# Laser_Array.net
KiCad netlist of a schematic drawn in EAGLE
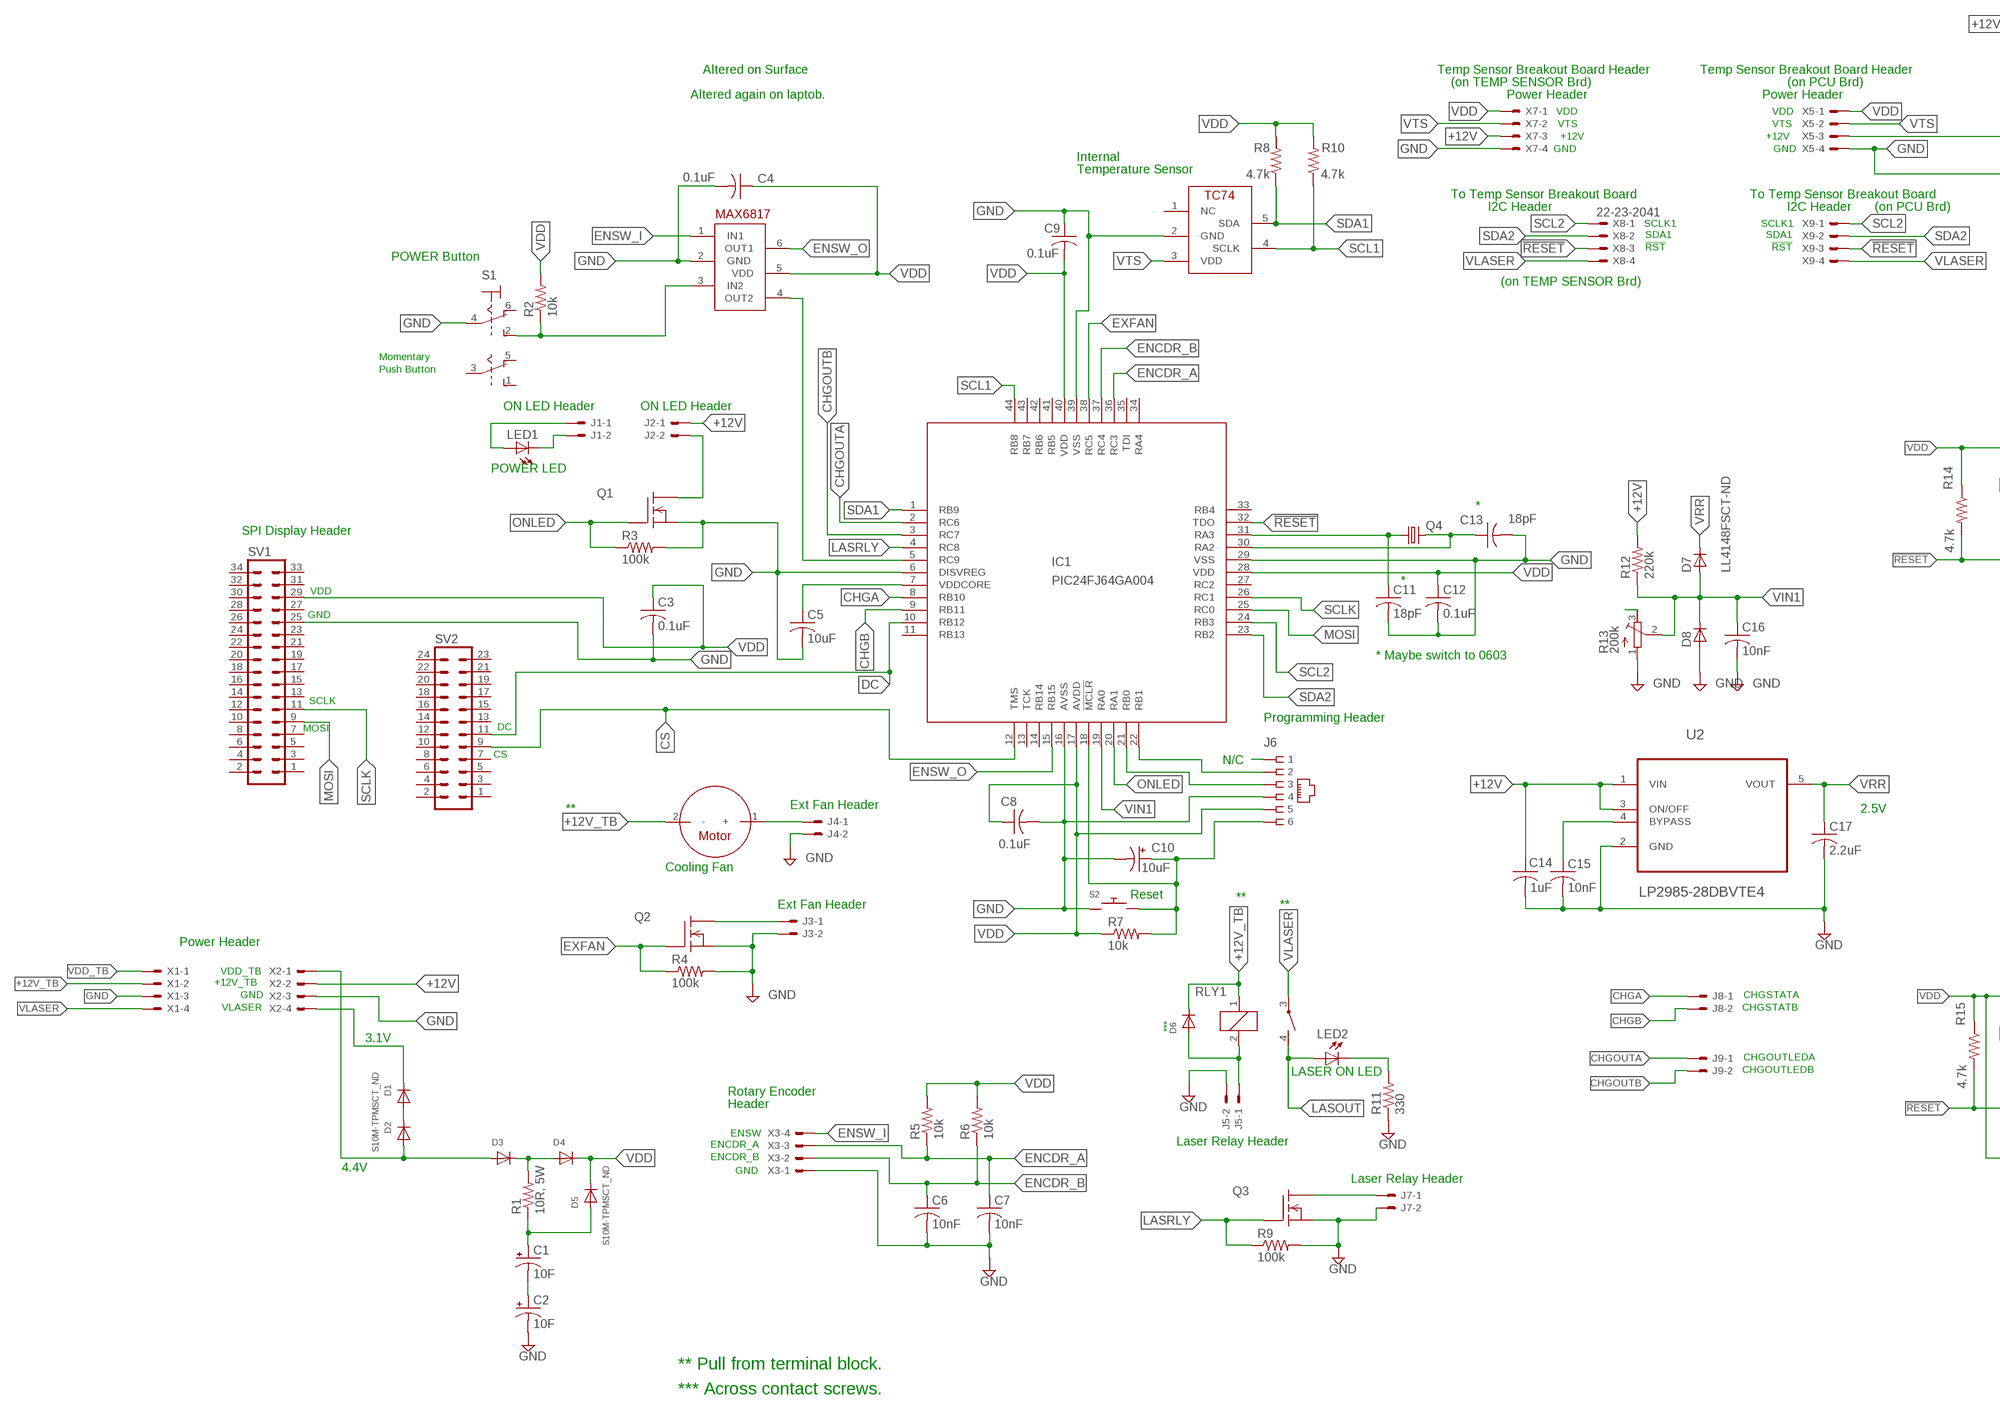
[diagram p0: schematic, sheet 1, part 1 of 2]
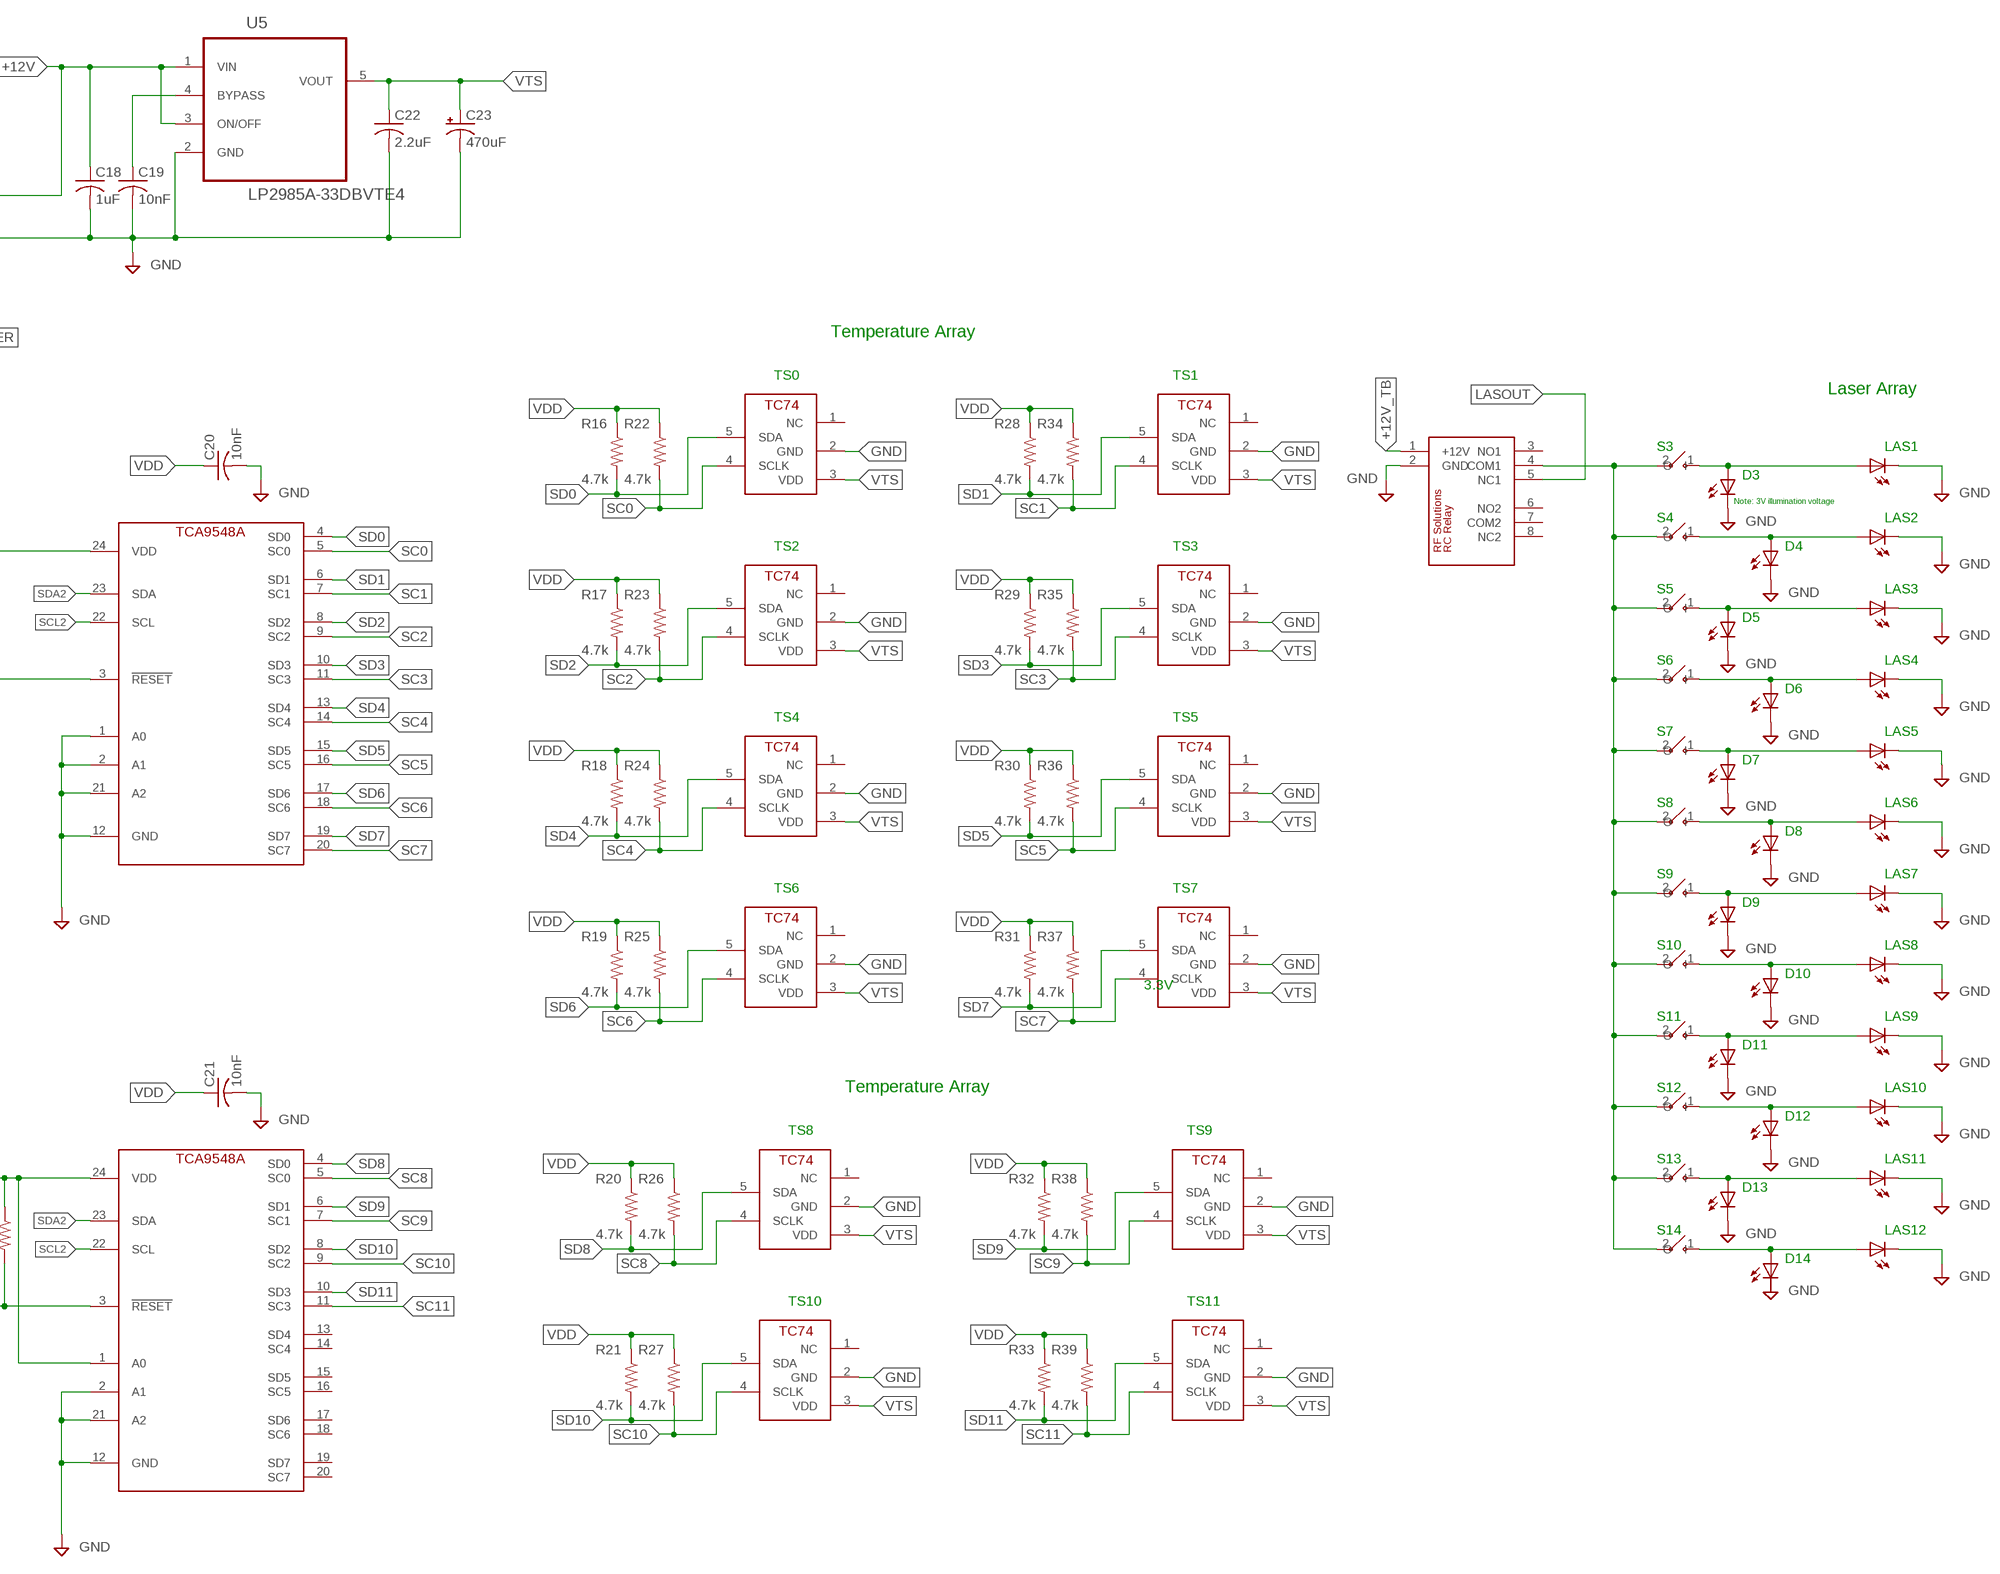
[diagram p1: schematic, sheet 1, part 2 of 2]

(export (version "E")
  (design (tool "Eeschema 10.0.6"))
  (components
    (comp (ref "C1")
      (value "10F")
      (footprint "eagle-import:E5-10,5")
      (libsource (lib "eagle-import") (part "CPOL-USE5-10.5"))
    )
    (comp (ref "C2")
      (value "10F")
      (footprint "eagle-import:E5-10,5")
      (libsource (lib "eagle-import") (part "CPOL-USE5-10.5"))
    )
    (comp (ref "C3")
      (value "0.1uF")
      (footprint "eagle-import:C0805")
      (libsource (lib "eagle-import") (part "C-USC0805"))
    )
    (comp (ref "C4")
      (value "0.1uF")
      (footprint "eagle-import:C0805")
      (libsource (lib "eagle-import") (part "C-USC0805"))
    )
    (comp (ref "C5")
      (value "10uF")
      (footprint "eagle-import:C0805")
      (libsource (lib "eagle-import") (part "C-USC0805"))
    )
    (comp (ref "C6")
      (value "10nF")
      (footprint "eagle-import:C0805")
      (libsource (lib "eagle-import") (part "C-USC0805"))
    )
    (comp (ref "C7")
      (value "10nF")
      (footprint "eagle-import:C0805")
      (libsource (lib "eagle-import") (part "C-USC0805"))
    )
    (comp (ref "C8")
      (value "0.1uF")
      (footprint "eagle-import:C0805")
      (libsource (lib "eagle-import") (part "C-USC0805"))
    )
    (comp (ref "C9")
      (value "0.1uF")
      (footprint "eagle-import:C0805")
      (libsource (lib "eagle-import") (part "C-USC0805"))
    )
    (comp (ref "C10")
      (value "10uF")
      (footprint "eagle-import:CAP3X3")
      (libsource (lib "eagle-import") (part "CAP3X3"))
    )
    (comp (ref "C11")
      (value "18pF")
      (footprint "eagle-import:C0805")
      (libsource (lib "eagle-import") (part "C-USC0805"))
    )
    (comp (ref "C12")
      (value "0.1uF")
      (footprint "eagle-import:C0805")
      (libsource (lib "eagle-import") (part "C-USC0805"))
    )
    (comp (ref "C13")
      (value "18pF")
      (footprint "eagle-import:C0805")
      (libsource (lib "eagle-import") (part "C-USC0805"))
    )
    (comp (ref "C14")
      (value "1uF")
      (footprint "eagle-import:C0805")
      (libsource (lib "eagle-import") (part "C-USC0805"))
    )
    (comp (ref "C15")
      (value "10nF")
      (footprint "eagle-import:C0805")
      (libsource (lib "eagle-import") (part "C-USC0805"))
    )
    (comp (ref "C16")
      (value "10nF")
      (footprint "eagle-import:C0805")
      (libsource (lib "eagle-import") (part "C-USC0805"))
    )
    (comp (ref "C17")
      (value "2.2uF")
      (footprint "eagle-import:C0805")
      (libsource (lib "eagle-import") (part "C-USC0805"))
    )
    (comp (ref "C18")
      (value "1uF")
      (footprint "eagle-import:C0805")
      (libsource (lib "eagle-import") (part "C-USC0805"))
    )
    (comp (ref "C19")
      (value "10nF")
      (footprint "eagle-import:C0805")
      (libsource (lib "eagle-import") (part "C-USC0805"))
    )
    (comp (ref "C20")
      (value "10nF")
      (footprint "eagle-import:C0805")
      (libsource (lib "eagle-import") (part "C-USC0805"))
    )
    (comp (ref "C21")
      (value "10nF")
      (footprint "eagle-import:C0805")
      (libsource (lib "eagle-import") (part "C-USC0805"))
    )
    (comp (ref "C22")
      (value "2.2uF")
      (footprint "eagle-import:C0805")
      (libsource (lib "eagle-import") (part "C-USC0805"))
    )
    (comp (ref "C23")
      (value "470uF")
      (footprint "eagle-import:PANASONIC_F")
      (libsource (lib "eagle-import") (part "CPOL-USF"))
    )
    (comp (ref "D1")
      (value "S10M-TPMSCT_ND")
      (footprint "eagle-import:S10M-TPMSCT-ND")
      (libsource (lib "eagle-import") (part "S10M-TPMSCT_ND"))
    )
    (comp (ref "D2")
      (value "641-1014-6-ND")
      (footprint "eagle-import:SOD-123")
      (libsource (lib "eagle-import") (part "DIODESOD-123"))
    )
    (comp (ref "D3")
      (value "641-1014-6-ND")
      (footprint "eagle-import:SOD-123")
      (libsource (lib "eagle-import") (part "DIODESOD-123"))
    )
    (comp (ref "D4")
      (value "641-1014-6-ND")
      (footprint "eagle-import:SOD-123")
      (libsource (lib "eagle-import") (part "DIODESOD-123"))
    )
    (comp (ref "D5")
      (value "S10M-TPMSCT_ND")
      (footprint "eagle-import:S10M-TPMSCT-ND")
      (libsource (lib "eagle-import") (part "S10M-TPMSCT_ND"))
    )
    (comp (ref "D6")
      (value "641-1014-6-ND")
      (footprint "eagle-import:SOD-123")
      (libsource (lib "eagle-import") (part "DIODESOD-123"))
    )
    (comp (ref "D7")
      (value "LL4148FSCT-ND")
      (footprint "eagle-import:SOD80")
      (libsource (lib "eagle-import") (part "D-SOD-80"))
    )
    (comp (ref "D8")
      (value "LL4148FSCT-ND")
      (footprint "eagle-import:SOD80")
      (libsource (lib "eagle-import") (part "D-SOD-80"))
    )
    (comp (ref "IC1")
      (value "PIC24FJ64GA004")
      (footprint "eagle-import:TQFP44")
      (fields (field (name "MPN") "PIC24FJ64GA004-E/PT"))
      (libsource (lib "eagle-import") (part "PIC24FJ64GA004"))
    )
    (comp (ref "J1")
      (value "22-23-2021")
      (footprint "eagle-import:22-23-2021")
      (fields (field (name "MF") "MOLEX"))
      (libsource (lib "eagle-import") (part "22-23-2021"))
    )
    (comp (ref "J2")
      (value "22-23-2021")
      (footprint "eagle-import:22-23-2021")
      (fields (field (name "MF") "MOLEX"))
      (libsource (lib "eagle-import") (part "22-23-2021"))
    )
    (comp (ref "J3")
      (value "22-23-2021")
      (footprint "eagle-import:22-23-2021")
      (fields (field (name "MF") "MOLEX"))
      (libsource (lib "eagle-import") (part "22-23-2021"))
    )
    (comp (ref "J4")
      (value "22-23-2021")
      (footprint "eagle-import:22-23-2021")
      (fields (field (name "MF") "MOLEX"))
      (libsource (lib "eagle-import") (part "22-23-2021"))
    )
    (comp (ref "J5")
      (value "22-23-2021")
      (footprint "eagle-import:22-23-2021")
      (fields (field (name "MF") "MOLEX"))
      (libsource (lib "eagle-import") (part "22-23-2021"))
    )
    (comp (ref "J6")
      (value "RJ_25")
      (footprint "eagle-import:RJ11-NO_SHIELD")
      (libsource (lib "eagle-import") (part "RJ_25"))
    )
    (comp (ref "J7")
      (value "22-23-2021")
      (footprint "eagle-import:22-23-2021")
      (fields (field (name "MF") "MOLEX"))
      (libsource (lib "eagle-import") (part "22-23-2021"))
    )
    (comp (ref "J8")
      (value "22-23-2021")
      (footprint "eagle-import:22-23-2021")
      (fields (field (name "MF") "MOLEX"))
      (libsource (lib "eagle-import") (part "22-23-2021"))
    )
    (comp (ref "J9")
      (value "22-23-2021")
      (footprint "eagle-import:22-23-2021")
      (fields (field (name "MF") "MOLEX"))
      (libsource (lib "eagle-import") (part "22-23-2021"))
    )
    (comp (ref "LED1")
      (value "LEDA5MM")
      (footprint "eagle-import:LED5MM")
      (libsource (lib "eagle-import") (part "LEDA5MM"))
    )
    (comp (ref "LED2")
      (value "LEDA5MM")
      (footprint "eagle-import:LED5MM")
      (libsource (lib "eagle-import") (part "LEDA5MM"))
    )
    (comp (ref "LED3")
      (value "LED3MM")
      (footprint "eagle-import:LED3MM")
      (libsource (lib "eagle-import") (part "LED3MM"))
    )
    (comp (ref "LED4")
      (value "LED3MM")
      (footprint "eagle-import:LED3MM")
      (libsource (lib "eagle-import") (part "LED3MM"))
    )
    (comp (ref "LED5")
      (value "LED3MM")
      (footprint "eagle-import:LED3MM")
      (libsource (lib "eagle-import") (part "LED3MM"))
    )
    (comp (ref "LED6")
      (value "LED3MM")
      (footprint "eagle-import:LED3MM")
      (libsource (lib "eagle-import") (part "LED3MM"))
    )
    (comp (ref "LED7")
      (value "LED3MM")
      (footprint "eagle-import:LED3MM")
      (libsource (lib "eagle-import") (part "LED3MM"))
    )
    (comp (ref "LED8")
      (value "LED3MM")
      (footprint "eagle-import:LED3MM")
      (libsource (lib "eagle-import") (part "LED3MM"))
    )
    (comp (ref "LED9")
      (value "LED3MM")
      (footprint "eagle-import:LED3MM")
      (libsource (lib "eagle-import") (part "LED3MM"))
    )
    (comp (ref "LED10")
      (value "LED3MM")
      (footprint "eagle-import:LED3MM")
      (libsource (lib "eagle-import") (part "LED3MM"))
    )
    (comp (ref "LED11")
      (value "LED3MM")
      (footprint "eagle-import:LED3MM")
      (libsource (lib "eagle-import") (part "LED3MM"))
    )
    (comp (ref "LED12")
      (value "LED3MM")
      (footprint "eagle-import:LED3MM")
      (libsource (lib "eagle-import") (part "LED3MM"))
    )
    (comp (ref "LED13")
      (value "LED3MM")
      (footprint "eagle-import:LED3MM")
      (libsource (lib "eagle-import") (part "LED3MM"))
    )
    (comp (ref "LED14")
      (value "LED3MM")
      (footprint "eagle-import:LED3MM")
      (libsource (lib "eagle-import") (part "LED3MM"))
    )
    (comp (ref "LED15")
      (value "LED3MM")
      (footprint "eagle-import:LED3MM")
      (libsource (lib "eagle-import") (part "LED3MM"))
    )
    (comp (ref "LED16")
      (value "LED3MM")
      (footprint "eagle-import:LED3MM")
      (libsource (lib "eagle-import") (part "LED3MM"))
    )
    (comp (ref "LED17")
      (value "LED3MM")
      (footprint "eagle-import:LED3MM")
      (libsource (lib "eagle-import") (part "LED3MM"))
    )
    (comp (ref "LED18")
      (value "LED3MM")
      (footprint "eagle-import:LED3MM")
      (libsource (lib "eagle-import") (part "LED3MM"))
    )
    (comp (ref "LED19")
      (value "LED3MM")
      (footprint "eagle-import:LED3MM")
      (libsource (lib "eagle-import") (part "LED3MM"))
    )
    (comp (ref "LED20")
      (value "LED3MM")
      (footprint "eagle-import:LED3MM")
      (libsource (lib "eagle-import") (part "LED3MM"))
    )
    (comp (ref "LED21")
      (value "LED3MM")
      (footprint "eagle-import:LED3MM")
      (libsource (lib "eagle-import") (part "LED3MM"))
    )
    (comp (ref "LED22")
      (value "LED3MM")
      (footprint "eagle-import:LED3MM")
      (libsource (lib "eagle-import") (part "LED3MM"))
    )
    (comp (ref "LED23")
      (value "LED3MM")
      (footprint "eagle-import:LED3MM")
      (libsource (lib "eagle-import") (part "LED3MM"))
    )
    (comp (ref "LED24")
      (value "LED3MM")
      (footprint "eagle-import:LED3MM")
      (libsource (lib "eagle-import") (part "LED3MM"))
    )
    (comp (ref "LED25")
      (value "LED3MM")
      (footprint "eagle-import:LED3MM")
      (libsource (lib "eagle-import") (part "LED3MM"))
    )
    (comp (ref "LED26")
      (value "LED3MM")
      (footprint "eagle-import:LED3MM")
      (libsource (lib "eagle-import") (part "LED3MM"))
    )
    (comp (ref "M1")
      (value "MOTOR")
      (footprint "eagle-import:22-23-2021")
      (libsource (lib "eagle-import") (part "MOTOR"))
    )
    (comp (ref "Q1")
      (value "QS5U34CT-ND_MOSFET_N_CHANNEL")
      (footprint "eagle-import:SOT23-5L")
      (libsource (lib "eagle-import") (part "QS5U34CT-ND_MOSFET_N_CHANNEL"))
    )
    (comp (ref "Q2")
      (value "QS5U34CT-ND_MOSFET_N_CHANNEL")
      (footprint "eagle-import:SOT23-5L")
      (libsource (lib "eagle-import") (part "QS5U34CT-ND_MOSFET_N_CHANNEL"))
    )
    (comp (ref "Q3")
      (value "QS5U34CT-ND_MOSFET_N_CHANNEL")
      (footprint "eagle-import:SOT23-5L")
      (libsource (lib "eagle-import") (part "QS5U34CT-ND_MOSFET_N_CHANNEL"))
    )
    (comp (ref "Q4")
      (value "CRYSTALSM49")
      (footprint "eagle-import:SM49")
      (libsource (lib "eagle-import") (part "CRYSTALSM49"))
    )
    (comp (ref "R1")
      (value "10R, 5W")
      (footprint "eagle-import:RESISTOR5W")
      (libsource (lib "eagle-import") (part "RESISTOR5W"))
    )
    (comp (ref "R2")
      (value "10k")
      (footprint "eagle-import:R0805")
      (libsource (lib "eagle-import") (part "R-US_R0805"))
    )
    (comp (ref "R3")
      (value "100k")
      (footprint "eagle-import:R0805")
      (libsource (lib "eagle-import") (part "R-US_R0805"))
    )
    (comp (ref "R4")
      (value "100k")
      (footprint "eagle-import:R0805")
      (libsource (lib "eagle-import") (part "R-US_R0805"))
    )
    (comp (ref "R5")
      (value "10k")
      (footprint "eagle-import:M0805")
      (libsource (lib "eagle-import") (part "R-US_M0805"))
    )
    (comp (ref "R6")
      (value "10k")
      (footprint "eagle-import:M0805")
      (libsource (lib "eagle-import") (part "R-US_M0805"))
    )
    (comp (ref "R7")
      (value "10k")
      (footprint "eagle-import:R0805")
      (libsource (lib "eagle-import") (part "R-US_R0805"))
    )
    (comp (ref "R8")
      (value "4.7k")
      (footprint "eagle-import:M0805")
      (libsource (lib "eagle-import") (part "R-US_M0805"))
    )
    (comp (ref "R9")
      (value "100k")
      (footprint "eagle-import:R0805")
      (libsource (lib "eagle-import") (part "R-US_R0805"))
    )
    (comp (ref "R10")
      (value "4.7k")
      (footprint "eagle-import:M0805")
      (libsource (lib "eagle-import") (part "R-US_M0805"))
    )
    (comp (ref "R11")
      (value "330")
      (footprint "eagle-import:R0805")
      (libsource (lib "eagle-import") (part "R-US_R0805"))
    )
    (comp (ref "R12")
      (value "220k")
      (footprint "eagle-import:M0805")
      (libsource (lib "eagle-import") (part "R-US_M0805"))
    )
    (comp (ref "R13")
      (value "200k")
      (footprint "eagle-import:RTRIM3224X")
      (libsource (lib "eagle-import") (part "R-TRIMM3224X"))
    )
    (comp (ref "R14")
      (value "4.7k")
      (footprint "eagle-import:M0805")
      (libsource (lib "eagle-import") (part "R-US_M0805"))
    )
    (comp (ref "R15")
      (value "4.7k")
      (footprint "eagle-import:M0805")
      (libsource (lib "eagle-import") (part "R-US_M0805"))
    )
    (comp (ref "R16")
      (value "4.7k")
      (footprint "eagle-import:M0805")
      (libsource (lib "eagle-import") (part "R-US_M0805"))
    )
    (comp (ref "R17")
      (value "4.7k")
      (footprint "eagle-import:M0805")
      (libsource (lib "eagle-import") (part "R-US_M0805"))
    )
    (comp (ref "R18")
      (value "4.7k")
      (footprint "eagle-import:M0805")
      (libsource (lib "eagle-import") (part "R-US_M0805"))
    )
    (comp (ref "R19")
      (value "4.7k")
      (footprint "eagle-import:M0805")
      (libsource (lib "eagle-import") (part "R-US_M0805"))
    )
    (comp (ref "R20")
      (value "4.7k")
      (footprint "eagle-import:M0805")
      (libsource (lib "eagle-import") (part "R-US_M0805"))
    )
    (comp (ref "R21")
      (value "4.7k")
      (footprint "eagle-import:M0805")
      (libsource (lib "eagle-import") (part "R-US_M0805"))
    )
    (comp (ref "R22")
      (value "4.7k")
      (footprint "eagle-import:M0805")
      (libsource (lib "eagle-import") (part "R-US_M0805"))
    )
    (comp (ref "R23")
      (value "4.7k")
      (footprint "eagle-import:M0805")
      (libsource (lib "eagle-import") (part "R-US_M0805"))
    )
    (comp (ref "R24")
      (value "4.7k")
      (footprint "eagle-import:M0805")
      (libsource (lib "eagle-import") (part "R-US_M0805"))
    )
    (comp (ref "R25")
      (value "4.7k")
      (footprint "eagle-import:M0805")
      (libsource (lib "eagle-import") (part "R-US_M0805"))
    )
    (comp (ref "R26")
      (value "4.7k")
      (footprint "eagle-import:M0805")
      (libsource (lib "eagle-import") (part "R-US_M0805"))
    )
    (comp (ref "R27")
      (value "4.7k")
      (footprint "eagle-import:M0805")
      (libsource (lib "eagle-import") (part "R-US_M0805"))
    )
    (comp (ref "R28")
      (value "4.7k")
      (footprint "eagle-import:M0805")
      (libsource (lib "eagle-import") (part "R-US_M0805"))
    )
    (comp (ref "R29")
      (value "4.7k")
      (footprint "eagle-import:M0805")
      (libsource (lib "eagle-import") (part "R-US_M0805"))
    )
    (comp (ref "R30")
      (value "4.7k")
      (footprint "eagle-import:M0805")
      (libsource (lib "eagle-import") (part "R-US_M0805"))
    )
    (comp (ref "R31")
      (value "4.7k")
      (footprint "eagle-import:M0805")
      (libsource (lib "eagle-import") (part "R-US_M0805"))
    )
    (comp (ref "R32")
      (value "4.7k")
      (footprint "eagle-import:M0805")
      (libsource (lib "eagle-import") (part "R-US_M0805"))
    )
    (comp (ref "R33")
      (value "4.7k")
      (footprint "eagle-import:M0805")
      (libsource (lib "eagle-import") (part "R-US_M0805"))
    )
    (comp (ref "R34")
      (value "4.7k")
      (footprint "eagle-import:M0805")
      (libsource (lib "eagle-import") (part "R-US_M0805"))
    )
    (comp (ref "R35")
      (value "4.7k")
      (footprint "eagle-import:M0805")
      (libsource (lib "eagle-import") (part "R-US_M0805"))
    )
    (comp (ref "R36")
      (value "4.7k")
      (footprint "eagle-import:M0805")
      (libsource (lib "eagle-import") (part "R-US_M0805"))
    )
    (comp (ref "R37")
      (value "4.7k")
      (footprint "eagle-import:M0805")
      (libsource (lib "eagle-import") (part "R-US_M0805"))
    )
    (comp (ref "R38")
      (value "4.7k")
      (footprint "eagle-import:M0805")
      (libsource (lib "eagle-import") (part "R-US_M0805"))
    )
    (comp (ref "R39")
      (value "4.7k")
      (footprint "eagle-import:M0805")
      (libsource (lib "eagle-import") (part "R-US_M0805"))
    )
    (comp (ref "RLY1")
      (value "RELAY_SPST")
      (footprint "eagle-import:RELAY_SPST")
      (libsource (lib "eagle-import") (part "RELAY_SPST"))
    )
    (comp (ref "RLY2")
      (value "RF_SOLUTIONS_RELAY")
      (footprint "eagle-import:RF_SOLUTIONS_RELAY")
      (libsource (lib "eagle-import") (part "RF_SOLUTIONS_RELAY"))
    )
    (comp (ref "S1")
      (value "DPDT_TOGGLE")
      (footprint "eagle-import:22-23-2061")
      (libsource (lib "eagle-import") (part "DPDT_TOGGLE"))
    )
    (comp (ref "S2")
      (value "TACT_PB")
      (footprint "eagle-import:PUSHBUTTON_SMD_SJ")
      (libsource (lib "eagle-import") (part "TACT_PB"))
    )
    (comp (ref "S3")
      (value "TC74")
      (footprint "eagle-import:SOT23-5L")
      (libsource (lib "eagle-import") (part "TC74"))
    )
    (comp (ref "S4")
      (value "TC74")
      (footprint "eagle-import:SOT23-5L")
      (libsource (lib "eagle-import") (part "TC74"))
    )
    (comp (ref "S5")
      (value "TC74")
      (footprint "eagle-import:SOT23-5L")
      (libsource (lib "eagle-import") (part "TC74"))
    )
    (comp (ref "S6")
      (value "TC74")
      (footprint "eagle-import:SOT23-5L")
      (libsource (lib "eagle-import") (part "TC74"))
    )
    (comp (ref "S7")
      (value "TC74")
      (footprint "eagle-import:SOT23-5L")
      (libsource (lib "eagle-import") (part "TC74"))
    )
    (comp (ref "S8")
      (value "TC74")
      (footprint "eagle-import:SOT23-5L")
      (libsource (lib "eagle-import") (part "TC74"))
    )
    (comp (ref "S9")
      (value "TC74")
      (footprint "eagle-import:SOT23-5L")
      (libsource (lib "eagle-import") (part "TC74"))
    )
    (comp (ref "S10")
      (value "TC74")
      (footprint "eagle-import:SOT23-5L")
      (libsource (lib "eagle-import") (part "TC74"))
    )
    (comp (ref "S11")
      (value "TC74")
      (footprint "eagle-import:SOT23-5L")
      (libsource (lib "eagle-import") (part "TC74"))
    )
    (comp (ref "S12")
      (value "TC74")
      (footprint "eagle-import:SOT23-5L")
      (libsource (lib "eagle-import") (part "TC74"))
    )
    (comp (ref "S13")
      (value "TC74")
      (footprint "eagle-import:SOT23-5L")
      (libsource (lib "eagle-import") (part "TC74"))
    )
    (comp (ref "S14")
      (value "TC74")
      (footprint "eagle-import:SOT23-5L")
      (libsource (lib "eagle-import") (part "TC74"))
    )
    (comp (ref "S15")
      (value "TC74")
      (footprint "eagle-import:SOT23-5L")
      (libsource (lib "eagle-import") (part "TC74"))
    )
    (comp (ref "S16")
      (value "TOGGLE_SPST")
      (footprint "eagle-import:22-23-2021")
      (libsource (lib "eagle-import") (part "TOGGLE_SPST"))
    )
    (comp (ref "S17")
      (value "TOGGLE_SPST")
      (footprint "eagle-import:22-23-2021")
      (libsource (lib "eagle-import") (part "TOGGLE_SPST"))
    )
    (comp (ref "S18")
      (value "TOGGLE_SPST")
      (footprint "eagle-import:22-23-2021")
      (libsource (lib "eagle-import") (part "TOGGLE_SPST"))
    )
    (comp (ref "S19")
      (value "TOGGLE_SPST")
      (footprint "eagle-import:22-23-2021")
      (libsource (lib "eagle-import") (part "TOGGLE_SPST"))
    )
    (comp (ref "S20")
      (value "TOGGLE_SPST")
      (footprint "eagle-import:22-23-2021")
      (libsource (lib "eagle-import") (part "TOGGLE_SPST"))
    )
    (comp (ref "S21")
      (value "TOGGLE_SPST")
      (footprint "eagle-import:22-23-2021")
      (libsource (lib "eagle-import") (part "TOGGLE_SPST"))
    )
    (comp (ref "S22")
      (value "TOGGLE_SPST")
      (footprint "eagle-import:22-23-2021")
      (libsource (lib "eagle-import") (part "TOGGLE_SPST"))
    )
    (comp (ref "S23")
      (value "TOGGLE_SPST")
      (footprint "eagle-import:22-23-2021")
      (libsource (lib "eagle-import") (part "TOGGLE_SPST"))
    )
    (comp (ref "S24")
      (value "TOGGLE_SPST")
      (footprint "eagle-import:22-23-2021")
      (libsource (lib "eagle-import") (part "TOGGLE_SPST"))
    )
    (comp (ref "S25")
      (value "TOGGLE_SPST")
      (footprint "eagle-import:22-23-2021")
      (libsource (lib "eagle-import") (part "TOGGLE_SPST"))
    )
    (comp (ref "S26")
      (value "TOGGLE_SPST")
      (footprint "eagle-import:22-23-2021")
      (libsource (lib "eagle-import") (part "TOGGLE_SPST"))
    )
    (comp (ref "S27")
      (value "TOGGLE_SPST")
      (footprint "eagle-import:22-23-2021")
      (libsource (lib "eagle-import") (part "TOGGLE_SPST"))
    )
    (comp (ref "SV1")
      (value "MA17-2W")
      (footprint "eagle-import:MA17-2W")
      (libsource (lib "eagle-import") (part "MA17-2W"))
    )
    (comp (ref "SV2")
      (value "MA12-2")
      (footprint "eagle-import:MA12-2")
      (libsource (lib "eagle-import") (part "MA12-2"))
    )
    (comp (ref "U1")
      (value "MAX6817")
      (footprint "eagle-import:SOT23-6")
      (libsource (lib "eagle-import") (part "MAX6817"))
    )
    (comp (ref "U2")
      (value "LP2985-28DBVTE4")
      (footprint "eagle-import:SOT95P280X145-5N")
      (libsource (lib "eagle-import") (part "LP2985-28DBVTE4"))
    )
    (comp (ref "U3")
      (value "TCA9548A")
      (footprint "eagle-import:TSSOP24")
      (libsource (lib "eagle-import") (part "TCA9548A"))
    )
    (comp (ref "U4")
      (value "TCA9548A")
      (footprint "eagle-import:TSSOP24")
      (libsource (lib "eagle-import") (part "TCA9548A"))
    )
    (comp (ref "U5")
      (value "LP2985A-33DBVTE4")
      (footprint "eagle-import:SOT95P280X145-5N")
      (libsource (lib "eagle-import") (part "LP2985A-33DBVTE4"))
    )
    (comp (ref "X1")
      (value "22-23-2041")
      (footprint "eagle-import:22-23-2041")
      (fields (field (name "MF") "MOLEX"))
      (libsource (lib "eagle-import") (part "22-23-2041"))
    )
    (comp (ref "X2")
      (value "22-23-2041")
      (footprint "eagle-import:22-23-2041")
      (fields (field (name "MF") "MOLEX"))
      (libsource (lib "eagle-import") (part "22-23-2041"))
    )
    (comp (ref "X3")
      (value "22-23-2041")
      (footprint "eagle-import:22-23-2041")
      (fields (field (name "MF") "MOLEX"))
      (libsource (lib "eagle-import") (part "22-23-2041"))
    )
    (comp (ref "X5")
      (value "22-23-2041")
      (footprint "eagle-import:22-23-2041")
      (fields (field (name "MF") "MOLEX"))
      (libsource (lib "eagle-import") (part "22-23-2041"))
    )
    (comp (ref "X7")
      (value "22-23-2041")
      (footprint "eagle-import:22-23-2041")
      (fields (field (name "MF") "MOLEX"))
      (libsource (lib "eagle-import") (part "22-23-2041"))
    )
    (comp (ref "X8")
      (value "22-23-2041")
      (footprint "eagle-import:22-23-2041")
      (fields (field (name "MF") "MOLEX"))
      (libsource (lib "eagle-import") (part "22-23-2041"))
    )
    (comp (ref "X9")
      (value "22-23-2041")
      (footprint "eagle-import:22-23-2041")
      (fields (field (name "MF") "MOLEX"))
      (libsource (lib "eagle-import") (part "22-23-2041"))
    )
  )
  (nets
    (net (code "1") (name "+12V") (class "Default")
      (node (ref "C14") (pin "1") (pinfunction "1_1") (pintype "passive"))
      (node (ref "C18") (pin "1") (pinfunction "1_1") (pintype "passive"))
      (node (ref "J2") (pin "1") (pinfunction "S_1") (pintype "passive"))
      (node (ref "R12") (pin "2") (pinfunction "2_2") (pintype "passive"))
      (node (ref "U2") (pin "1") (pinfunction "VIN_1") (pintype "power_in"))
      (node (ref "U2") (pin "3") (pinfunction "ON/OFF_3") (pintype "input"))
      (node (ref "U5") (pin "1") (pinfunction "VIN_1") (pintype "power_in"))
      (node (ref "U5") (pin "3") (pinfunction "ON/OFF_3") (pintype "input"))
      (node (ref "X2") (pin "2") (pinfunction "S_2") (pintype "passive"))
      (node (ref "X5") (pin "3") (pinfunction "S_3") (pintype "passive"))
      (node (ref "X7") (pin "3") (pinfunction "S_3") (pintype "passive"))
    )
    (net (code "2") (name "+12V_TB") (class "Default")
      (node (ref "D6") (pin "C") (pinfunction "C_C") (pintype "passive"))
      (node (ref "M1") (pin "2") (pinfunction "-_2") (pintype "bidirectional"))
      (node (ref "RLY1") (pin "1") (pinfunction "1_1") (pintype "passive"))
      (node (ref "RLY2") (pin "1") (pinfunction "+12V_1") (pintype "power_in"))
      (node (ref "X1") (pin "2") (pinfunction "S_2") (pintype "passive"))
    )
    (net (code "3") (name "/~{RESET}") (class "Default")
      (node (ref "IC1") (pin "32") (pinfunction "TDO_32") (pintype "output"))
      (node (ref "R14") (pin "2") (pinfunction "2_2") (pintype "passive"))
      (node (ref "R15") (pin "2") (pinfunction "2_2") (pintype "passive"))
      (node (ref "U3") (pin "3") (pinfunction "~{RESET}_3") (pintype "bidirectional"))
      (node (ref "U4") (pin "3") (pinfunction "~{RESET}_3") (pintype "bidirectional"))
      (node (ref "X8") (pin "3") (pinfunction "S_3") (pintype "passive"))
      (node (ref "X9") (pin "3") (pinfunction "S_3") (pintype "passive"))
    )
    (net (code "4") (name "CHGA") (class "Default")
      (node (ref "IC1") (pin "8") (pinfunction "RB10_8") (pintype "bidirectional"))
      (node (ref "J8") (pin "1") (pinfunction "S_1") (pintype "passive"))
    )
    (net (code "5") (name "CHGB") (class "Default")
      (node (ref "IC1") (pin "9") (pinfunction "RB11_9") (pintype "bidirectional"))
      (node (ref "J8") (pin "2") (pinfunction "S_2") (pintype "passive"))
    )
    (net (code "6") (name "CHGOUTA") (class "Default")
      (node (ref "IC1") (pin "2") (pinfunction "RC6_2") (pintype "bidirectional"))
      (node (ref "J9") (pin "1") (pinfunction "S_1") (pintype "passive"))
    )
    (net (code "7") (name "CHGOUTB") (class "Default")
      (node (ref "IC1") (pin "3") (pinfunction "RC7_3") (pintype "bidirectional"))
      (node (ref "J9") (pin "2") (pinfunction "S_2") (pintype "passive"))
    )
    (net (code "8") (name "CS") (class "Default")
      (node (ref "IC1") (pin "12") (pinfunction "TMS_12") (pintype "input"))
      (node (ref "SV2") (pin "9") (pinfunction "9_9") (pintype "passive"))
    )
    (net (code "9") (name "DC") (class "Default")
      (node (ref "IC1") (pin "10") (pinfunction "RB12_10") (pintype "bidirectional"))
      (node (ref "SV2") (pin "11") (pinfunction "11_11") (pintype "passive"))
    )
    (net (code "10") (name "ENCDR_A") (class "Default")
      (node (ref "C7") (pin "1") (pinfunction "1_1") (pintype "passive"))
      (node (ref "IC1") (pin "36") (pinfunction "RC3_36") (pintype "bidirectional"))
      (node (ref "R5") (pin "1") (pinfunction "1_1") (pintype "passive"))
      (node (ref "X3") (pin "3") (pinfunction "S_3") (pintype "passive"))
    )
    (net (code "11") (name "ENCDR_B") (class "Default")
      (node (ref "C6") (pin "1") (pinfunction "1_1") (pintype "passive"))
      (node (ref "IC1") (pin "37") (pinfunction "RC4_37") (pintype "bidirectional"))
      (node (ref "R6") (pin "1") (pinfunction "1_1") (pintype "passive"))
      (node (ref "X3") (pin "2") (pinfunction "S_2") (pintype "passive"))
    )
    (net (code "12") (name "ENSW_I") (class "Default")
      (node (ref "U1") (pin "1") (pinfunction "IN1_1") (pintype "input"))
      (node (ref "X3") (pin "4") (pinfunction "S_4") (pintype "passive"))
    )
    (net (code "13") (name "ENSW_O") (class "Default")
      (node (ref "IC1") (pin "15") (pinfunction "RB15_15") (pintype "bidirectional"))
      (node (ref "U1") (pin "6") (pinfunction "OUT1_6") (pintype "output"))
    )
    (net (code "14") (name "EXFAN") (class "Default")
      (node (ref "IC1") (pin "38") (pinfunction "RC5_38") (pintype "bidirectional"))
      (node (ref "Q2") (pin "1") (pinfunction "G_1") (pintype "passive"))
      (node (ref "R4") (pin "1") (pinfunction "1_1") (pintype "passive"))
    )
    (net (code "15") (name "GND") (class "Default")
      (node (ref "C10") (pin "-") (pinfunction "-_-") (pintype "passive"))
      (node (ref "C11") (pin "2") (pinfunction "2_2") (pintype "passive"))
      (node (ref "C12") (pin "2") (pinfunction "2_2") (pintype "passive"))
      (node (ref "C13") (pin "2") (pinfunction "2_2") (pintype "passive"))
      (node (ref "C14") (pin "2") (pinfunction "2_2") (pintype "passive"))
      (node (ref "C15") (pin "2") (pinfunction "2_2") (pintype "passive"))
      (node (ref "C16") (pin "2") (pinfunction "2_2") (pintype "passive"))
      (node (ref "C17") (pin "2") (pinfunction "2_2") (pintype "passive"))
      (node (ref "C18") (pin "2") (pinfunction "2_2") (pintype "passive"))
      (node (ref "C19") (pin "2") (pinfunction "2_2") (pintype "passive"))
      (node (ref "C2") (pin "-") (pinfunction "-_-") (pintype "passive"))
      (node (ref "C20") (pin "2") (pinfunction "2_2") (pintype "passive"))
      (node (ref "C21") (pin "2") (pinfunction "2_2") (pintype "passive"))
      (node (ref "C22") (pin "2") (pinfunction "2_2") (pintype "passive"))
      (node (ref "C23") (pin "-") (pinfunction "-_-") (pintype "passive"))
      (node (ref "C3") (pin "2") (pinfunction "2_2") (pintype "passive"))
      (node (ref "C4") (pin "2") (pinfunction "2_2") (pintype "passive"))
      (node (ref "C5") (pin "2") (pinfunction "2_2") (pintype "passive"))
      (node (ref "C6") (pin "2") (pinfunction "2_2") (pintype "passive"))
      (node (ref "C7") (pin "2") (pinfunction "2_2") (pintype "passive"))
      (node (ref "C8") (pin "2") (pinfunction "2_2") (pintype "passive"))
      (node (ref "C9") (pin "1") (pinfunction "1_1") (pintype "passive"))
      (node (ref "D8") (pin "2") (pinfunction "A_2") (pintype "passive"))
      (node (ref "IC1") (pin "16") (pinfunction "AVSS_16") (pintype "power_in"))
      (node (ref "IC1") (pin "29") (pinfunction "VSS_29") (pintype "power_in"))
      (node (ref "IC1") (pin "39") (pinfunction "VSS_39") (pintype "power_in"))
      (node (ref "IC1") (pin "6") (pinfunction "DISVREG_6") (pintype "passive"))
      (node (ref "J3") (pin "2") (pinfunction "S_2") (pintype "passive"))
      (node (ref "J4") (pin "2") (pinfunction "S_2") (pintype "passive"))
      (node (ref "J5") (pin "2") (pinfunction "S_2") (pintype "passive"))
      (node (ref "J6") (pin "4") (pinfunction "4_4") (pintype "passive"))
      (node (ref "J7") (pin "2") (pinfunction "S_2") (pintype "passive"))
      (node (ref "LED10") (pin "K") (pinfunction "C_K") (pintype "passive"))
      (node (ref "LED11") (pin "K") (pinfunction "C_K") (pintype "passive"))
      (node (ref "LED12") (pin "K") (pinfunction "C_K") (pintype "passive"))
      (node (ref "LED13") (pin "K") (pinfunction "C_K") (pintype "passive"))
      (node (ref "LED15") (pin "K") (pinfunction "C_K") (pintype "passive"))
      (node (ref "LED16") (pin "K") (pinfunction "C_K") (pintype "passive"))
      (node (ref "LED17") (pin "K") (pinfunction "C_K") (pintype "passive"))
      (node (ref "LED18") (pin "K") (pinfunction "C_K") (pintype "passive"))
      (node (ref "LED19") (pin "K") (pinfunction "C_K") (pintype "passive"))
      (node (ref "LED20") (pin "K") (pinfunction "C_K") (pintype "passive"))
      (node (ref "LED21") (pin "K") (pinfunction "C_K") (pintype "passive"))
      (node (ref "LED22") (pin "K") (pinfunction "C_K") (pintype "passive"))
      (node (ref "LED23") (pin "K") (pinfunction "C_K") (pintype "passive"))
      (node (ref "LED24") (pin "K") (pinfunction "C_K") (pintype "passive"))
      (node (ref "LED25") (pin "K") (pinfunction "C_K") (pintype "passive"))
      (node (ref "LED26") (pin "K") (pinfunction "C_K") (pintype "passive"))
      (node (ref "LED3") (pin "K") (pinfunction "C_K") (pintype "passive"))
      (node (ref "LED4") (pin "K") (pinfunction "C_K") (pintype "passive"))
      (node (ref "LED5") (pin "K") (pinfunction "C_K") (pintype "passive"))
      (node (ref "LED6") (pin "K") (pinfunction "C_K") (pintype "passive"))
      (node (ref "LED7") (pin "K") (pinfunction "C_K") (pintype "passive"))
      (node (ref "LED8") (pin "K") (pinfunction "C_K") (pintype "passive"))
      (node (ref "LED9") (pin "K") (pinfunction "C_K") (pintype "passive"))
      (node (ref "Q1") (pin "2") (pinfunction "S_2") (pintype "passive"))
      (node (ref "Q2") (pin "2") (pinfunction "S_2") (pintype "passive"))
      (node (ref "Q3") (pin "2") (pinfunction "S_2") (pintype "passive"))
      (node (ref "R11") (pin "1") (pinfunction "1_1") (pintype "passive"))
      (node (ref "R13") (pin "1") (pinfunction "A_1") (pintype "passive"))
      (node (ref "R3") (pin "2") (pinfunction "2_2") (pintype "passive"))
      (node (ref "R4") (pin "2") (pinfunction "2_2") (pintype "passive"))
      (node (ref "R9") (pin "2") (pinfunction "2_2") (pintype "passive"))
      (node (ref "RLY2") (pin "2") (pinfunction "GND_2") (pintype "power_in"))
      (node (ref "S1") (pin "4") (pinfunction "P_4") (pintype "passive"))
      (node (ref "S10") (pin "2") (pinfunction "GND_2") (pintype "bidirectional"))
      (node (ref "S11") (pin "2") (pinfunction "GND_2") (pintype "bidirectional"))
      (node (ref "S12") (pin "2") (pinfunction "GND_2") (pintype "bidirectional"))
      (node (ref "S13") (pin "2") (pinfunction "GND_2") (pintype "bidirectional"))
      (node (ref "S14") (pin "2") (pinfunction "GND_2") (pintype "bidirectional"))
      (node (ref "S15") (pin "2") (pinfunction "GND_2") (pintype "bidirectional"))
      (node (ref "S2") (pin "1") (pinfunction "1_1") (pintype "passive"))
      (node (ref "S2") (pin "2") (pinfunction "1_2") (pintype "passive"))
      (node (ref "S3") (pin "2") (pinfunction "GND_2") (pintype "bidirectional"))
      (node (ref "S4") (pin "2") (pinfunction "GND_2") (pintype "bidirectional"))
      (node (ref "S5") (pin "2") (pinfunction "GND_2") (pintype "bidirectional"))
      (node (ref "S6") (pin "2") (pinfunction "GND_2") (pintype "bidirectional"))
      (node (ref "S7") (pin "2") (pinfunction "GND_2") (pintype "bidirectional"))
      (node (ref "S8") (pin "2") (pinfunction "GND_2") (pintype "bidirectional"))
      (node (ref "S9") (pin "2") (pinfunction "GND_2") (pintype "bidirectional"))
      (node (ref "SV1") (pin "25") (pinfunction "25_25") (pintype "passive"))
      (node (ref "U1") (pin "2") (pinfunction "GND_2") (pintype "power_in"))
      (node (ref "U2") (pin "2") (pinfunction "GND_2") (pintype "passive"))
      (node (ref "U3") (pin "1") (pinfunction "A0_1") (pintype "bidirectional"))
      (node (ref "U3") (pin "12") (pinfunction "GND_12") (pintype "bidirectional"))
      (node (ref "U3") (pin "2") (pinfunction "A1_2") (pintype "bidirectional"))
      (node (ref "U3") (pin "21") (pinfunction "A2_21") (pintype "bidirectional"))
      (node (ref "U4") (pin "12") (pinfunction "GND_12") (pintype "bidirectional"))
      (node (ref "U4") (pin "2") (pinfunction "A1_2") (pintype "bidirectional"))
      (node (ref "U4") (pin "21") (pinfunction "A2_21") (pintype "bidirectional"))
      (node (ref "U5") (pin "2") (pinfunction "GND_2") (pintype "passive"))
      (node (ref "X1") (pin "3") (pinfunction "S_3") (pintype "passive"))
      (node (ref "X2") (pin "3") (pinfunction "S_3") (pintype "passive"))
      (node (ref "X3") (pin "1") (pinfunction "S_1") (pintype "passive"))
      (node (ref "X5") (pin "4") (pinfunction "S_4") (pintype "passive"))
      (node (ref "X7") (pin "4") (pinfunction "S_4") (pintype "passive"))
    )
    (net (code "16") (name "LASOUT") (class "Default")
      (node (ref "LED2") (pin "A") (pinfunction "A_A") (pintype "passive"))
      (node (ref "RLY1") (pin "4") (pinfunction "S_4") (pintype "passive"))
      (node (ref "RLY2") (pin "5") (pinfunction "NC1_5") (pintype "bidirectional"))
    )
    (net (code "17") (name "LASRLY") (class "Default")
      (node (ref "IC1") (pin "4") (pinfunction "RC8_4") (pintype "bidirectional"))
      (node (ref "Q3") (pin "1") (pinfunction "G_1") (pintype "passive"))
      (node (ref "R9") (pin "1") (pinfunction "1_1") (pintype "passive"))
    )
    (net (code "18") (name "MOSI") (class "Default")
      (node (ref "IC1") (pin "25") (pinfunction "RC0_25") (pintype "bidirectional"))
      (node (ref "SV1") (pin "9") (pinfunction "9_9") (pintype "passive"))
    )
    (net (code "19") (name "Net-(C1-Pad+)") (class "Default")
      (node (ref "C1") (pin "+") (pinfunction "+_+") (pintype "passive"))
      (node (ref "D5") (pin "A") (pinfunction "A_A") (pintype "passive"))
      (node (ref "R1") (pin "1") (pinfunction "1_1") (pintype "passive"))
    )
    (net (code "20") (name "Net-(C1-Pad-)") (class "Default")
      (node (ref "C1") (pin "-") (pinfunction "-_-") (pintype "passive"))
      (node (ref "C2") (pin "+") (pinfunction "+_+") (pintype "passive"))
    )
    (net (code "21") (name "Net-(D1-PadA)") (class "Default")
      (node (ref "D1") (pin "A") (pinfunction "A_A") (pintype "passive"))
      (node (ref "D2") (pin "C") (pinfunction "C_C") (pintype "passive"))
    )
    (net (code "22") (name "Net-(D3-PadC)") (class "Default")
      (node (ref "D3") (pin "C") (pinfunction "C_C") (pintype "passive"))
      (node (ref "D4") (pin "A") (pinfunction "A_A") (pintype "passive"))
      (node (ref "R1") (pin "2") (pinfunction "2_2") (pintype "passive"))
    )
    (net (code "23") (name "Net-(IC1-RA2)") (class "Default")
      (node (ref "C13") (pin "1") (pinfunction "1_1") (pintype "passive"))
      (node (ref "IC1") (pin "30") (pinfunction "RA2_30") (pintype "bidirectional"))
      (node (ref "Q4") (pin "2") (pinfunction "2_2") (pintype "passive"))
    )
    (net (code "24") (name "Net-(IC1-RA3)") (class "Default")
      (node (ref "C11") (pin "1") (pinfunction "1_1") (pintype "passive"))
      (node (ref "IC1") (pin "31") (pinfunction "RA3_31") (pintype "bidirectional"))
      (node (ref "Q4") (pin "1") (pinfunction "1_1") (pintype "passive"))
    )
    (net (code "25") (name "Net-(IC1-RB0)") (class "Default")
      (node (ref "IC1") (pin "21") (pinfunction "RB0_21") (pintype "bidirectional"))
      (node (ref "J6") (pin "3") (pinfunction "3_3") (pintype "passive"))
    )
    (net (code "26") (name "Net-(IC1-RB1)") (class "Default")
      (node (ref "IC1") (pin "22") (pinfunction "RB1_22") (pintype "bidirectional"))
      (node (ref "J6") (pin "2") (pinfunction "2_2") (pintype "passive"))
    )
    (net (code "27") (name "Net-(IC1-RC9)") (class "Default")
      (node (ref "IC1") (pin "5") (pinfunction "RC9_5") (pintype "bidirectional"))
      (node (ref "U1") (pin "4") (pinfunction "OUT2_4") (pintype "output"))
    )
    (net (code "28") (name "Net-(IC1-VDDCORE)") (class "Default")
      (node (ref "C5") (pin "1") (pinfunction "1_1") (pintype "passive"))
      (node (ref "IC1") (pin "7") (pinfunction "VDDCORE_7") (pintype "power_in"))
    )
    (net (code "29") (name "Net-(IC1-~{MCLR})") (class "Default")
      (node (ref "C10") (pin "+") (pinfunction "+_+") (pintype "passive"))
      (node (ref "IC1") (pin "18") (pinfunction "~{MCLR}_18") (pintype "bidirectional"))
      (node (ref "J6") (pin "6") (pinfunction "6_6") (pintype "passive"))
      (node (ref "R7") (pin "2") (pinfunction "2_2") (pintype "passive"))
      (node (ref "S2") (pin "3") (pinfunction "2_3") (pintype "passive"))
      (node (ref "S2") (pin "4") (pinfunction "2_4") (pintype "passive"))
    )
    (net (code "30") (name "Net-(J1A-S)") (class "Default")
      (node (ref "J1") (pin "1") (pinfunction "S_1") (pintype "passive"))
      (node (ref "LED1") (pin "A") (pinfunction "A_A") (pintype "passive"))
    )
    (net (code "31") (name "Net-(J1B-S)") (class "Default")
      (node (ref "J1") (pin "2") (pinfunction "S_2") (pintype "passive"))
      (node (ref "LED1") (pin "K") (pinfunction "C_K") (pintype "passive"))
    )
    (net (code "32") (name "Net-(J2B-S)") (class "Default")
      (node (ref "J2") (pin "2") (pinfunction "S_2") (pintype "passive"))
      (node (ref "Q1") (pin "5") (pinfunction "D_5") (pintype "passive"))
    )
    (net (code "33") (name "Net-(J3A-S)") (class "Default")
      (node (ref "J3") (pin "1") (pinfunction "S_1") (pintype "passive"))
      (node (ref "Q2") (pin "5") (pinfunction "D_5") (pintype "passive"))
    )
    (net (code "34") (name "Net-(J4A-S)") (class "Default")
      (node (ref "J4") (pin "1") (pinfunction "S_1") (pintype "passive"))
      (node (ref "M1") (pin "1") (pinfunction "+_1") (pintype "bidirectional"))
    )
    (net (code "35") (name "Net-(J5A-S)") (class "Default")
      (node (ref "D6") (pin "A") (pinfunction "A_A") (pintype "passive"))
      (node (ref "J5") (pin "1") (pinfunction "S_1") (pintype "passive"))
      (node (ref "RLY1") (pin "2") (pinfunction "2_2") (pintype "passive"))
    )
    (net (code "36") (name "Net-(J7A-S)") (class "Default")
      (node (ref "J7") (pin "1") (pinfunction "S_1") (pintype "passive"))
      (node (ref "Q3") (pin "5") (pinfunction "D_5") (pintype "passive"))
    )
    (net (code "37") (name "Net-(LED2-C)") (class "Default")
      (node (ref "LED2") (pin "K") (pinfunction "C_K") (pintype "passive"))
      (node (ref "R11") (pin "2") (pinfunction "2_2") (pintype "passive"))
    )
    (net (code "38") (name "Net-(RLY2-COM1)") (class "Default")
      (node (ref "RLY2") (pin "4") (pinfunction "COM1_4") (pintype "bidirectional"))
      (node (ref "S16") (pin "2") (pinfunction "I_2") (pintype "bidirectional"))
      (node (ref "S17") (pin "2") (pinfunction "I_2") (pintype "bidirectional"))
      (node (ref "S18") (pin "2") (pinfunction "I_2") (pintype "bidirectional"))
      (node (ref "S19") (pin "2") (pinfunction "I_2") (pintype "bidirectional"))
      (node (ref "S20") (pin "2") (pinfunction "I_2") (pintype "bidirectional"))
      (node (ref "S21") (pin "2") (pinfunction "I_2") (pintype "bidirectional"))
      (node (ref "S22") (pin "2") (pinfunction "I_2") (pintype "bidirectional"))
      (node (ref "S23") (pin "2") (pinfunction "I_2") (pintype "bidirectional"))
      (node (ref "S24") (pin "2") (pinfunction "I_2") (pintype "bidirectional"))
      (node (ref "S25") (pin "2") (pinfunction "I_2") (pintype "bidirectional"))
      (node (ref "S26") (pin "2") (pinfunction "I_2") (pintype "bidirectional"))
      (node (ref "S27") (pin "2") (pinfunction "I_2") (pintype "bidirectional"))
    )
    (net (code "39") (name "Net-(S1-S)") (class "Default")
      (node (ref "R2") (pin "1") (pinfunction "1_1") (pintype "passive"))
      (node (ref "S1") (pin "2") (pinfunction "S_2") (pintype "passive"))
      (node (ref "U1") (pin "3") (pinfunction "IN2_3") (pintype "input"))
    )
    (net (code "40") (name "Net-(S16-O)") (class "Default")
      (node (ref "LED15") (pin "A") (pinfunction "A_A") (pintype "passive"))
      (node (ref "LED3") (pin "A") (pinfunction "A_A") (pintype "passive"))
      (node (ref "S16") (pin "1") (pinfunction "O_1") (pintype "bidirectional"))
    )
    (net (code "41") (name "Net-(S17-O)") (class "Default")
      (node (ref "LED16") (pin "A") (pinfunction "A_A") (pintype "passive"))
      (node (ref "LED9") (pin "A") (pinfunction "A_A") (pintype "passive"))
      (node (ref "S17") (pin "1") (pinfunction "O_1") (pintype "bidirectional"))
    )
    (net (code "42") (name "Net-(S18-O)") (class "Default")
      (node (ref "LED17") (pin "A") (pinfunction "A_A") (pintype "passive"))
      (node (ref "LED4") (pin "A") (pinfunction "A_A") (pintype "passive"))
      (node (ref "S18") (pin "1") (pinfunction "O_1") (pintype "bidirectional"))
    )
    (net (code "43") (name "Net-(S19-O)") (class "Default")
      (node (ref "LED10") (pin "A") (pinfunction "A_A") (pintype "passive"))
      (node (ref "LED18") (pin "A") (pinfunction "A_A") (pintype "passive"))
      (node (ref "S19") (pin "1") (pinfunction "O_1") (pintype "bidirectional"))
    )
    (net (code "44") (name "Net-(S20-O)") (class "Default")
      (node (ref "LED19") (pin "A") (pinfunction "A_A") (pintype "passive"))
      (node (ref "LED5") (pin "A") (pinfunction "A_A") (pintype "passive"))
      (node (ref "S20") (pin "1") (pinfunction "O_1") (pintype "bidirectional"))
    )
    (net (code "45") (name "Net-(S21-O)") (class "Default")
      (node (ref "LED11") (pin "A") (pinfunction "A_A") (pintype "passive"))
      (node (ref "LED20") (pin "A") (pinfunction "A_A") (pintype "passive"))
      (node (ref "S21") (pin "1") (pinfunction "O_1") (pintype "bidirectional"))
    )
    (net (code "46") (name "Net-(S22-O)") (class "Default")
      (node (ref "LED21") (pin "A") (pinfunction "A_A") (pintype "passive"))
      (node (ref "LED6") (pin "A") (pinfunction "A_A") (pintype "passive"))
      (node (ref "S22") (pin "1") (pinfunction "O_1") (pintype "bidirectional"))
    )
    (net (code "47") (name "Net-(S23-O)") (class "Default")
      (node (ref "LED12") (pin "A") (pinfunction "A_A") (pintype "passive"))
      (node (ref "LED22") (pin "A") (pinfunction "A_A") (pintype "passive"))
      (node (ref "S23") (pin "1") (pinfunction "O_1") (pintype "bidirectional"))
    )
    (net (code "48") (name "Net-(S24-O)") (class "Default")
      (node (ref "LED23") (pin "A") (pinfunction "A_A") (pintype "passive"))
      (node (ref "LED7") (pin "A") (pinfunction "A_A") (pintype "passive"))
      (node (ref "S24") (pin "1") (pinfunction "O_1") (pintype "bidirectional"))
    )
    (net (code "49") (name "Net-(S25-O)") (class "Default")
      (node (ref "LED13") (pin "A") (pinfunction "A_A") (pintype "passive"))
      (node (ref "LED24") (pin "A") (pinfunction "A_A") (pintype "passive"))
      (node (ref "S25") (pin "1") (pinfunction "O_1") (pintype "bidirectional"))
    )
    (net (code "50") (name "Net-(S26-O)") (class "Default")
      (node (ref "LED25") (pin "A") (pinfunction "A_A") (pintype "passive"))
      (node (ref "LED8") (pin "A") (pinfunction "A_A") (pintype "passive"))
      (node (ref "S26") (pin "1") (pinfunction "O_1") (pintype "bidirectional"))
    )
    (net (code "51") (name "Net-(S27-O)") (class "Default")
      (node (ref "LED14") (pin "A") (pinfunction "A_A") (pintype "passive"))
      (node (ref "LED26") (pin "A") (pinfunction "A_A") (pintype "passive"))
      (node (ref "S27") (pin "1") (pinfunction "O_1") (pintype "bidirectional"))
    )
    (net (code "52") (name "Net-(U2-BYPASS)") (class "Default")
      (node (ref "C15") (pin "1") (pinfunction "1_1") (pintype "passive"))
      (node (ref "U2") (pin "4") (pinfunction "BYPASS_4") (pintype "input"))
    )
    (net (code "53") (name "Net-(U5-BYPASS)") (class "Default")
      (node (ref "C19") (pin "1") (pinfunction "1_1") (pintype "passive"))
      (node (ref "U5") (pin "4") (pinfunction "BYPASS_4") (pintype "input"))
    )
    (net (code "54") (name "ONLED") (class "Default")
      (node (ref "IC1") (pin "20") (pinfunction "RA1_20") (pintype "bidirectional"))
      (node (ref "Q1") (pin "1") (pinfunction "G_1") (pintype "passive"))
      (node (ref "R3") (pin "1") (pinfunction "1_1") (pintype "passive"))
    )
    (net (code "55") (name "SC0") (class "Default")
      (node (ref "R22") (pin "2") (pinfunction "2_2") (pintype "passive"))
      (node (ref "S4") (pin "4") (pinfunction "SCLK_4") (pintype "bidirectional"))
      (node (ref "U3") (pin "5") (pinfunction "SC0_5") (pintype "bidirectional"))
    )
    (net (code "56") (name "SC1") (class "Default")
      (node (ref "R34") (pin "2") (pinfunction "2_2") (pintype "passive"))
      (node (ref "S10") (pin "4") (pinfunction "SCLK_4") (pintype "bidirectional"))
      (node (ref "U3") (pin "7") (pinfunction "SC1_7") (pintype "bidirectional"))
    )
    (net (code "57") (name "SC2") (class "Default")
      (node (ref "R23") (pin "2") (pinfunction "2_2") (pintype "passive"))
      (node (ref "S5") (pin "4") (pinfunction "SCLK_4") (pintype "bidirectional"))
      (node (ref "U3") (pin "9") (pinfunction "SC2_9") (pintype "bidirectional"))
    )
    (net (code "58") (name "SC3") (class "Default")
      (node (ref "R35") (pin "2") (pinfunction "2_2") (pintype "passive"))
      (node (ref "S11") (pin "4") (pinfunction "SCLK_4") (pintype "bidirectional"))
      (node (ref "U3") (pin "11") (pinfunction "SC3_11") (pintype "bidirectional"))
    )
    (net (code "59") (name "SC4") (class "Default")
      (node (ref "R24") (pin "2") (pinfunction "2_2") (pintype "passive"))
      (node (ref "S6") (pin "4") (pinfunction "SCLK_4") (pintype "bidirectional"))
      (node (ref "U3") (pin "14") (pinfunction "SC4_14") (pintype "bidirectional"))
    )
    (net (code "60") (name "SC5") (class "Default")
      (node (ref "R36") (pin "2") (pinfunction "2_2") (pintype "passive"))
      (node (ref "S12") (pin "4") (pinfunction "SCLK_4") (pintype "bidirectional"))
      (node (ref "U3") (pin "16") (pinfunction "SC5_16") (pintype "bidirectional"))
    )
    (net (code "61") (name "SC6") (class "Default")
      (node (ref "R25") (pin "2") (pinfunction "2_2") (pintype "passive"))
      (node (ref "S7") (pin "4") (pinfunction "SCLK_4") (pintype "bidirectional"))
      (node (ref "U3") (pin "18") (pinfunction "SC6_18") (pintype "bidirectional"))
    )
    (net (code "62") (name "SC7") (class "Default")
      (node (ref "R37") (pin "2") (pinfunction "2_2") (pintype "passive"))
      (node (ref "S13") (pin "4") (pinfunction "SCLK_4") (pintype "bidirectional"))
      (node (ref "U3") (pin "20") (pinfunction "SC7_20") (pintype "bidirectional"))
    )
    (net (code "63") (name "SC8") (class "Default")
      (node (ref "R26") (pin "2") (pinfunction "2_2") (pintype "passive"))
      (node (ref "S8") (pin "4") (pinfunction "SCLK_4") (pintype "bidirectional"))
      (node (ref "U4") (pin "5") (pinfunction "SC0_5") (pintype "bidirectional"))
    )
    (net (code "64") (name "SC9") (class "Default")
      (node (ref "R38") (pin "2") (pinfunction "2_2") (pintype "passive"))
      (node (ref "S14") (pin "4") (pinfunction "SCLK_4") (pintype "bidirectional"))
      (node (ref "U4") (pin "7") (pinfunction "SC1_7") (pintype "bidirectional"))
    )
    (net (code "65") (name "SC10") (class "Default")
      (node (ref "R27") (pin "2") (pinfunction "2_2") (pintype "passive"))
      (node (ref "S9") (pin "4") (pinfunction "SCLK_4") (pintype "bidirectional"))
      (node (ref "U4") (pin "9") (pinfunction "SC2_9") (pintype "bidirectional"))
    )
    (net (code "66") (name "SC11") (class "Default")
      (node (ref "R39") (pin "2") (pinfunction "2_2") (pintype "passive"))
      (node (ref "S15") (pin "4") (pinfunction "SCLK_4") (pintype "bidirectional"))
      (node (ref "U4") (pin "11") (pinfunction "SC3_11") (pintype "bidirectional"))
    )
    (net (code "67") (name "SCL1") (class "Default")
      (node (ref "IC1") (pin "44") (pinfunction "RB8_44") (pintype "bidirectional"))
      (node (ref "R10") (pin "1") (pinfunction "1_1") (pintype "passive"))
      (node (ref "S3") (pin "4") (pinfunction "SCLK_4") (pintype "bidirectional"))
    )
    (net (code "68") (name "SCL2") (class "Default")
      (node (ref "IC1") (pin "24") (pinfunction "RB3_24") (pintype "bidirectional"))
      (node (ref "U3") (pin "22") (pinfunction "SCL_22") (pintype "bidirectional"))
      (node (ref "U4") (pin "22") (pinfunction "SCL_22") (pintype "bidirectional"))
      (node (ref "X8") (pin "1") (pinfunction "S_1") (pintype "passive"))
      (node (ref "X9") (pin "1") (pinfunction "S_1") (pintype "passive"))
    )
    (net (code "69") (name "SCLK") (class "Default")
      (node (ref "IC1") (pin "26") (pinfunction "RC1_26") (pintype "bidirectional"))
      (node (ref "SV1") (pin "11") (pinfunction "11_11") (pintype "passive"))
    )
    (net (code "70") (name "SD0") (class "Default")
      (node (ref "R16") (pin "2") (pinfunction "2_2") (pintype "passive"))
      (node (ref "S4") (pin "5") (pinfunction "SDA_5") (pintype "bidirectional"))
      (node (ref "U3") (pin "4") (pinfunction "SD0_4") (pintype "bidirectional"))
    )
    (net (code "71") (name "SD1") (class "Default")
      (node (ref "R28") (pin "2") (pinfunction "2_2") (pintype "passive"))
      (node (ref "S10") (pin "5") (pinfunction "SDA_5") (pintype "bidirectional"))
      (node (ref "U3") (pin "6") (pinfunction "SD1_6") (pintype "bidirectional"))
    )
    (net (code "72") (name "SD2") (class "Default")
      (node (ref "R17") (pin "2") (pinfunction "2_2") (pintype "passive"))
      (node (ref "S5") (pin "5") (pinfunction "SDA_5") (pintype "bidirectional"))
      (node (ref "U3") (pin "8") (pinfunction "SD2_8") (pintype "bidirectional"))
    )
    (net (code "73") (name "SD3") (class "Default")
      (node (ref "R29") (pin "2") (pinfunction "2_2") (pintype "passive"))
      (node (ref "S11") (pin "5") (pinfunction "SDA_5") (pintype "bidirectional"))
      (node (ref "U3") (pin "10") (pinfunction "SD3_10") (pintype "bidirectional"))
    )
    (net (code "74") (name "SD4") (class "Default")
      (node (ref "R18") (pin "2") (pinfunction "2_2") (pintype "passive"))
      (node (ref "S6") (pin "5") (pinfunction "SDA_5") (pintype "bidirectional"))
      (node (ref "U3") (pin "13") (pinfunction "SD4_13") (pintype "bidirectional"))
    )
    (net (code "75") (name "SD5") (class "Default")
      (node (ref "R30") (pin "2") (pinfunction "2_2") (pintype "passive"))
      (node (ref "S12") (pin "5") (pinfunction "SDA_5") (pintype "bidirectional"))
      (node (ref "U3") (pin "15") (pinfunction "SD5_15") (pintype "bidirectional"))
    )
    (net (code "76") (name "SD6") (class "Default")
      (node (ref "R19") (pin "2") (pinfunction "2_2") (pintype "passive"))
      (node (ref "S7") (pin "5") (pinfunction "SDA_5") (pintype "bidirectional"))
      (node (ref "U3") (pin "17") (pinfunction "SD6_17") (pintype "bidirectional"))
    )
    (net (code "77") (name "SD7") (class "Default")
      (node (ref "R31") (pin "2") (pinfunction "2_2") (pintype "passive"))
      (node (ref "S13") (pin "5") (pinfunction "SDA_5") (pintype "bidirectional"))
      (node (ref "U3") (pin "19") (pinfunction "SD7_19") (pintype "bidirectional"))
    )
    (net (code "78") (name "SD8") (class "Default")
      (node (ref "R20") (pin "2") (pinfunction "2_2") (pintype "passive"))
      (node (ref "S8") (pin "5") (pinfunction "SDA_5") (pintype "bidirectional"))
      (node (ref "U4") (pin "4") (pinfunction "SD0_4") (pintype "bidirectional"))
    )
    (net (code "79") (name "SD9") (class "Default")
      (node (ref "R32") (pin "2") (pinfunction "2_2") (pintype "passive"))
      (node (ref "S14") (pin "5") (pinfunction "SDA_5") (pintype "bidirectional"))
      (node (ref "U4") (pin "6") (pinfunction "SD1_6") (pintype "bidirectional"))
    )
    (net (code "80") (name "SD10") (class "Default")
      (node (ref "R21") (pin "2") (pinfunction "2_2") (pintype "passive"))
      (node (ref "S9") (pin "5") (pinfunction "SDA_5") (pintype "bidirectional"))
      (node (ref "U4") (pin "8") (pinfunction "SD2_8") (pintype "bidirectional"))
    )
    (net (code "81") (name "SD11") (class "Default")
      (node (ref "R33") (pin "2") (pinfunction "2_2") (pintype "passive"))
      (node (ref "S15") (pin "5") (pinfunction "SDA_5") (pintype "bidirectional"))
      (node (ref "U4") (pin "10") (pinfunction "SD3_10") (pintype "bidirectional"))
    )
    (net (code "82") (name "SDA1") (class "Default")
      (node (ref "IC1") (pin "1") (pinfunction "RB9_1") (pintype "bidirectional"))
      (node (ref "R8") (pin "1") (pinfunction "1_1") (pintype "passive"))
      (node (ref "S3") (pin "5") (pinfunction "SDA_5") (pintype "bidirectional"))
    )
    (net (code "83") (name "SDA2") (class "Default")
      (node (ref "IC1") (pin "23") (pinfunction "RB2_23") (pintype "bidirectional"))
      (node (ref "U3") (pin "23") (pinfunction "SDA_23") (pintype "bidirectional"))
      (node (ref "U4") (pin "23") (pinfunction "SDA_23") (pintype "bidirectional"))
      (node (ref "X8") (pin "2") (pinfunction "S_2") (pintype "passive"))
      (node (ref "X9") (pin "2") (pinfunction "S_2") (pintype "passive"))
    )
    (net (code "84") (name "VDD") (class "Default")
      (node (ref "C12") (pin "1") (pinfunction "1_1") (pintype "passive"))
      (node (ref "C20") (pin "1") (pinfunction "1_1") (pintype "passive"))
      (node (ref "C21") (pin "1") (pinfunction "1_1") (pintype "passive"))
      (node (ref "C3") (pin "1") (pinfunction "1_1") (pintype "passive"))
      (node (ref "C4") (pin "1") (pinfunction "1_1") (pintype "passive"))
      (node (ref "C8") (pin "1") (pinfunction "1_1") (pintype "passive"))
      (node (ref "C9") (pin "2") (pinfunction "2_2") (pintype "passive"))
      (node (ref "D4") (pin "C") (pinfunction "C_C") (pintype "passive"))
      (node (ref "D5") (pin "C") (pinfunction "C_C") (pintype "passive"))
      (node (ref "IC1") (pin "17") (pinfunction "AVDD_17") (pintype "power_in"))
      (node (ref "IC1") (pin "28") (pinfunction "VDD_28") (pintype "power_in"))
      (node (ref "IC1") (pin "40") (pinfunction "VDD_40") (pintype "power_in"))
      (node (ref "J6") (pin "5") (pinfunction "5_5") (pintype "passive"))
      (node (ref "R10") (pin "2") (pinfunction "2_2") (pintype "passive"))
      (node (ref "R14") (pin "1") (pinfunction "1_1") (pintype "passive"))
      (node (ref "R15") (pin "1") (pinfunction "1_1") (pintype "passive"))
      (node (ref "R16") (pin "1") (pinfunction "1_1") (pintype "passive"))
      (node (ref "R17") (pin "1") (pinfunction "1_1") (pintype "passive"))
      (node (ref "R18") (pin "1") (pinfunction "1_1") (pintype "passive"))
      (node (ref "R19") (pin "1") (pinfunction "1_1") (pintype "passive"))
      (node (ref "R2") (pin "2") (pinfunction "2_2") (pintype "passive"))
      (node (ref "R20") (pin "1") (pinfunction "1_1") (pintype "passive"))
      (node (ref "R21") (pin "1") (pinfunction "1_1") (pintype "passive"))
      (node (ref "R22") (pin "1") (pinfunction "1_1") (pintype "passive"))
      (node (ref "R23") (pin "1") (pinfunction "1_1") (pintype "passive"))
      (node (ref "R24") (pin "1") (pinfunction "1_1") (pintype "passive"))
      (node (ref "R25") (pin "1") (pinfunction "1_1") (pintype "passive"))
      (node (ref "R26") (pin "1") (pinfunction "1_1") (pintype "passive"))
      (node (ref "R27") (pin "1") (pinfunction "1_1") (pintype "passive"))
      (node (ref "R28") (pin "1") (pinfunction "1_1") (pintype "passive"))
      (node (ref "R29") (pin "1") (pinfunction "1_1") (pintype "passive"))
      (node (ref "R30") (pin "1") (pinfunction "1_1") (pintype "passive"))
      (node (ref "R31") (pin "1") (pinfunction "1_1") (pintype "passive"))
      (node (ref "R32") (pin "1") (pinfunction "1_1") (pintype "passive"))
      (node (ref "R33") (pin "1") (pinfunction "1_1") (pintype "passive"))
      (node (ref "R34") (pin "1") (pinfunction "1_1") (pintype "passive"))
      (node (ref "R35") (pin "1") (pinfunction "1_1") (pintype "passive"))
      (node (ref "R36") (pin "1") (pinfunction "1_1") (pintype "passive"))
      (node (ref "R37") (pin "1") (pinfunction "1_1") (pintype "passive"))
      (node (ref "R38") (pin "1") (pinfunction "1_1") (pintype "passive"))
      (node (ref "R39") (pin "1") (pinfunction "1_1") (pintype "passive"))
      (node (ref "R5") (pin "2") (pinfunction "2_2") (pintype "passive"))
      (node (ref "R6") (pin "2") (pinfunction "2_2") (pintype "passive"))
      (node (ref "R7") (pin "1") (pinfunction "1_1") (pintype "passive"))
      (node (ref "R8") (pin "2") (pinfunction "2_2") (pintype "passive"))
      (node (ref "SV1") (pin "29") (pinfunction "29_29") (pintype "passive"))
      (node (ref "U1") (pin "5") (pinfunction "VDD_5") (pintype "power_in"))
      (node (ref "U3") (pin "24") (pinfunction "VDD_24") (pintype "bidirectional"))
      (node (ref "U4") (pin "1") (pinfunction "A0_1") (pintype "bidirectional"))
      (node (ref "U4") (pin "24") (pinfunction "VDD_24") (pintype "bidirectional"))
      (node (ref "X5") (pin "1") (pinfunction "S_1") (pintype "passive"))
      (node (ref "X7") (pin "1") (pinfunction "S_1") (pintype "passive"))
    )
    (net (code "85") (name "VDD_TB") (class "Default")
      (node (ref "D2") (pin "A") (pinfunction "A_A") (pintype "passive"))
      (node (ref "D3") (pin "A") (pinfunction "A_A") (pintype "passive"))
      (node (ref "X1") (pin "1") (pinfunction "S_1") (pintype "passive"))
      (node (ref "X2") (pin "1") (pinfunction "S_1") (pintype "passive"))
    )
    (net (code "86") (name "VIN1") (class "Default")
      (node (ref "C16") (pin "1") (pinfunction "1_1") (pintype "passive"))
      (node (ref "D7") (pin "2") (pinfunction "A_2") (pintype "passive"))
      (node (ref "D8") (pin "1") (pinfunction "C_1") (pintype "passive"))
      (node (ref "IC1") (pin "19") (pinfunction "RA0_19") (pintype "bidirectional"))
      (node (ref "R12") (pin "1") (pinfunction "1_1") (pintype "passive"))
      (node (ref "R13") (pin "2") (pinfunction "S_2") (pintype "passive"))
    )
    (net (code "87") (name "VLASER") (class "Default")
      (node (ref "D1") (pin "C") (pinfunction "C_C") (pintype "passive"))
      (node (ref "RLY1") (pin "3") (pinfunction "P_3") (pintype "passive"))
      (node (ref "X1") (pin "4") (pinfunction "S_4") (pintype "passive"))
      (node (ref "X2") (pin "4") (pinfunction "S_4") (pintype "passive"))
      (node (ref "X8") (pin "4") (pinfunction "S_4") (pintype "passive"))
      (node (ref "X9") (pin "4") (pinfunction "S_4") (pintype "passive"))
    )
    (net (code "88") (name "VRR") (class "Default")
      (node (ref "C17") (pin "1") (pinfunction "1_1") (pintype "passive"))
      (node (ref "D7") (pin "1") (pinfunction "C_1") (pintype "passive"))
      (node (ref "U2") (pin "5") (pinfunction "VOUT_5") (pintype "output"))
    )
    (net (code "89") (name "VTS") (class "Default")
      (node (ref "C22") (pin "1") (pinfunction "1_1") (pintype "passive"))
      (node (ref "C23") (pin "+") (pinfunction "+_+") (pintype "passive"))
      (node (ref "S10") (pin "3") (pinfunction "VDD_3") (pintype "bidirectional"))
      (node (ref "S11") (pin "3") (pinfunction "VDD_3") (pintype "bidirectional"))
      (node (ref "S12") (pin "3") (pinfunction "VDD_3") (pintype "bidirectional"))
      (node (ref "S13") (pin "3") (pinfunction "VDD_3") (pintype "bidirectional"))
      (node (ref "S14") (pin "3") (pinfunction "VDD_3") (pintype "bidirectional"))
      (node (ref "S15") (pin "3") (pinfunction "VDD_3") (pintype "bidirectional"))
      (node (ref "S3") (pin "3") (pinfunction "VDD_3") (pintype "bidirectional"))
      (node (ref "S4") (pin "3") (pinfunction "VDD_3") (pintype "bidirectional"))
      (node (ref "S5") (pin "3") (pinfunction "VDD_3") (pintype "bidirectional"))
      (node (ref "S6") (pin "3") (pinfunction "VDD_3") (pintype "bidirectional"))
      (node (ref "S7") (pin "3") (pinfunction "VDD_3") (pintype "bidirectional"))
      (node (ref "S8") (pin "3") (pinfunction "VDD_3") (pintype "bidirectional"))
      (node (ref "S9") (pin "3") (pinfunction "VDD_3") (pintype "bidirectional"))
      (node (ref "U5") (pin "5") (pinfunction "VOUT_5") (pintype "output"))
      (node (ref "X5") (pin "2") (pinfunction "S_2") (pintype "passive"))
      (node (ref "X7") (pin "2") (pinfunction "S_2") (pintype "passive"))
    )
    (net (code "90") (name "unconnected-(IC1-RA4-Pad34)") (class "Default")
      (node (ref "IC1") (pin "34") (pinfunction "RA4_34") (pintype "bidirectional"))
    )
    (net (code "91") (name "unconnected-(IC1-RB4-Pad33)") (class "Default")
      (node (ref "IC1") (pin "33") (pinfunction "RB4_33") (pintype "bidirectional"))
    )
    (net (code "92") (name "unconnected-(IC1-RB5-Pad41)") (class "Default")
      (node (ref "IC1") (pin "41") (pinfunction "RB5_41") (pintype "bidirectional"))
    )
    (net (code "93") (name "unconnected-(IC1-RB6-Pad42)") (class "Default")
      (node (ref "IC1") (pin "42") (pinfunction "RB6_42") (pintype "bidirectional"))
    )
    (net (code "94") (name "unconnected-(IC1-RB7-Pad43)") (class "Default")
      (node (ref "IC1") (pin "43") (pinfunction "RB7_43") (pintype "bidirectional"))
    )
    (net (code "95") (name "unconnected-(IC1-RB13-Pad11)") (class "Default")
      (node (ref "IC1") (pin "11") (pinfunction "RB13_11") (pintype "bidirectional"))
    )
    (net (code "96") (name "unconnected-(IC1-RB14-Pad14)") (class "Default")
      (node (ref "IC1") (pin "14") (pinfunction "RB14_14") (pintype "bidirectional"))
    )
    (net (code "97") (name "unconnected-(IC1-RC2-Pad27)") (class "Default")
      (node (ref "IC1") (pin "27") (pinfunction "RC2_27") (pintype "bidirectional"))
    )
    (net (code "98") (name "unconnected-(IC1-TCK-Pad13)") (class "Default")
      (node (ref "IC1") (pin "13") (pinfunction "TCK_13") (pintype "input"))
    )
    (net (code "99") (name "unconnected-(IC1-TDI-Pad35)") (class "Default")
      (node (ref "IC1") (pin "35") (pinfunction "TDI_35") (pintype "input"))
    )
    (net (code "100") (name "unconnected-(J6-Pad1)") (class "Default")
      (node (ref "J6") (pin "1") (pinfunction "1_1") (pintype "passive"))
    )
    (net (code "101") (name "unconnected-(LED14-C-PadK)") (class "Default")
      (node (ref "LED14") (pin "K") (pinfunction "C_K") (pintype "passive"))
    )
    (net (code "102") (name "unconnected-(R13-E-Pad3)") (class "Default")
      (node (ref "R13") (pin "3") (pinfunction "E_3") (pintype "passive"))
    )
    (net (code "103") (name "unconnected-(RLY2-COM2-Pad7)") (class "Default")
      (node (ref "RLY2") (pin "7") (pinfunction "COM2_7") (pintype "bidirectional"))
    )
    (net (code "104") (name "unconnected-(RLY2-NC2-Pad8)") (class "Default")
      (node (ref "RLY2") (pin "8") (pinfunction "NC2_8") (pintype "bidirectional"))
    )
    (net (code "105") (name "unconnected-(RLY2-NO1-Pad3)") (class "Default")
      (node (ref "RLY2") (pin "3") (pinfunction "NO1_3") (pintype "bidirectional"))
    )
    (net (code "106") (name "unconnected-(RLY2-NO2-Pad6)") (class "Default")
      (node (ref "RLY2") (pin "6") (pinfunction "NO2_6") (pintype "bidirectional"))
    )
    (net (code "107") (name "unconnected-(S1-O-Pad6)") (class "Default")
      (node (ref "S1") (pin "6") (pinfunction "O_6") (pintype "passive"))
    )
    (net (code "108") (name "unconnected-(S1-O1-Pad5)") (class "Default")
      (node (ref "S1") (pin "5") (pinfunction "O1_5") (pintype "passive"))
    )
    (net (code "109") (name "unconnected-(S1-P1-Pad3)") (class "Default")
      (node (ref "S1") (pin "3") (pinfunction "P1_3") (pintype "passive"))
    )
    (net (code "110") (name "unconnected-(S1-S1-Pad1)") (class "Default")
      (node (ref "S1") (pin "1") (pinfunction "S1_1") (pintype "passive"))
    )
    (net (code "111") (name "unconnected-(S3-NC-Pad1)") (class "Default")
      (node (ref "S3") (pin "1") (pinfunction "NC_1") (pintype "bidirectional"))
    )
    (net (code "112") (name "unconnected-(S4-NC-Pad1)") (class "Default")
      (node (ref "S4") (pin "1") (pinfunction "NC_1") (pintype "bidirectional"))
    )
    (net (code "113") (name "unconnected-(S5-NC-Pad1)") (class "Default")
      (node (ref "S5") (pin "1") (pinfunction "NC_1") (pintype "bidirectional"))
    )
    (net (code "114") (name "unconnected-(S6-NC-Pad1)") (class "Default")
      (node (ref "S6") (pin "1") (pinfunction "NC_1") (pintype "bidirectional"))
    )
    (net (code "115") (name "unconnected-(S7-NC-Pad1)") (class "Default")
      (node (ref "S7") (pin "1") (pinfunction "NC_1") (pintype "bidirectional"))
    )
    (net (code "116") (name "unconnected-(S8-NC-Pad1)") (class "Default")
      (node (ref "S8") (pin "1") (pinfunction "NC_1") (pintype "bidirectional"))
    )
    (net (code "117") (name "unconnected-(S9-NC-Pad1)") (class "Default")
      (node (ref "S9") (pin "1") (pinfunction "NC_1") (pintype "bidirectional"))
    )
    (net (code "118") (name "unconnected-(S10-NC-Pad1)") (class "Default")
      (node (ref "S10") (pin "1") (pinfunction "NC_1") (pintype "bidirectional"))
    )
    (net (code "119") (name "unconnected-(S11-NC-Pad1)") (class "Default")
      (node (ref "S11") (pin "1") (pinfunction "NC_1") (pintype "bidirectional"))
    )
    (net (code "120") (name "unconnected-(S12-NC-Pad1)") (class "Default")
      (node (ref "S12") (pin "1") (pinfunction "NC_1") (pintype "bidirectional"))
    )
    (net (code "121") (name "unconnected-(S13-NC-Pad1)") (class "Default")
      (node (ref "S13") (pin "1") (pinfunction "NC_1") (pintype "bidirectional"))
    )
    (net (code "122") (name "unconnected-(S14-NC-Pad1)") (class "Default")
      (node (ref "S14") (pin "1") (pinfunction "NC_1") (pintype "bidirectional"))
    )
    (net (code "123") (name "unconnected-(S15-NC-Pad1)") (class "Default")
      (node (ref "S15") (pin "1") (pinfunction "NC_1") (pintype "bidirectional"))
    )
    (net (code "124") (name "unconnected-(SV1-Pad1)") (class "Default")
      (node (ref "SV1") (pin "1") (pinfunction "1_1") (pintype "passive"))
    )
    (net (code "125") (name "unconnected-(SV1-Pad2)") (class "Default")
      (node (ref "SV1") (pin "2") (pinfunction "2_2") (pintype "passive"))
    )
    (net (code "126") (name "unconnected-(SV1-Pad3)") (class "Default")
      (node (ref "SV1") (pin "3") (pinfunction "3_3") (pintype "passive"))
    )
    (net (code "127") (name "unconnected-(SV1-Pad4)") (class "Default")
      (node (ref "SV1") (pin "4") (pinfunction "4_4") (pintype "passive"))
    )
    (net (code "128") (name "unconnected-(SV1-Pad5)") (class "Default")
      (node (ref "SV1") (pin "5") (pinfunction "5_5") (pintype "passive"))
    )
    (net (code "129") (name "unconnected-(SV1-Pad6)") (class "Default")
      (node (ref "SV1") (pin "6") (pinfunction "6_6") (pintype "passive"))
    )
    (net (code "130") (name "unconnected-(SV1-Pad7)") (class "Default")
      (node (ref "SV1") (pin "7") (pinfunction "7_7") (pintype "passive"))
    )
    (net (code "131") (name "unconnected-(SV1-Pad8)") (class "Default")
      (node (ref "SV1") (pin "8") (pinfunction "8_8") (pintype "passive"))
    )
    (net (code "132") (name "unconnected-(SV1-Pad10)") (class "Default")
      (node (ref "SV1") (pin "10") (pinfunction "10_10") (pintype "passive"))
    )
    (net (code "133") (name "unconnected-(SV1-Pad12)") (class "Default")
      (node (ref "SV1") (pin "12") (pinfunction "12_12") (pintype "passive"))
    )
    (net (code "134") (name "unconnected-(SV1-Pad13)") (class "Default")
      (node (ref "SV1") (pin "13") (pinfunction "13_13") (pintype "passive"))
    )
    (net (code "135") (name "unconnected-(SV1-Pad14)") (class "Default")
      (node (ref "SV1") (pin "14") (pinfunction "14_14") (pintype "passive"))
    )
    (net (code "136") (name "unconnected-(SV1-Pad15)") (class "Default")
      (node (ref "SV1") (pin "15") (pinfunction "15_15") (pintype "passive"))
    )
    (net (code "137") (name "unconnected-(SV1-Pad16)") (class "Default")
      (node (ref "SV1") (pin "16") (pinfunction "16_16") (pintype "passive"))
    )
    (net (code "138") (name "unconnected-(SV1-Pad17)") (class "Default")
      (node (ref "SV1") (pin "17") (pinfunction "17_17") (pintype "passive"))
    )
    (net (code "139") (name "unconnected-(SV1-Pad18)") (class "Default")
      (node (ref "SV1") (pin "18") (pinfunction "18_18") (pintype "passive"))
    )
    (net (code "140") (name "unconnected-(SV1-Pad19)") (class "Default")
      (node (ref "SV1") (pin "19") (pinfunction "19_19") (pintype "passive"))
    )
    (net (code "141") (name "unconnected-(SV1-Pad20)") (class "Default")
      (node (ref "SV1") (pin "20") (pinfunction "20_20") (pintype "passive"))
    )
    (net (code "142") (name "unconnected-(SV1-Pad21)") (class "Default")
      (node (ref "SV1") (pin "21") (pinfunction "21_21") (pintype "passive"))
    )
    (net (code "143") (name "unconnected-(SV1-Pad22)") (class "Default")
      (node (ref "SV1") (pin "22") (pinfunction "22_22") (pintype "passive"))
    )
    (net (code "144") (name "unconnected-(SV1-Pad23)") (class "Default")
      (node (ref "SV1") (pin "23") (pinfunction "23_23") (pintype "passive"))
    )
    (net (code "145") (name "unconnected-(SV1-Pad24)") (class "Default")
      (node (ref "SV1") (pin "24") (pinfunction "24_24") (pintype "passive"))
    )
    (net (code "146") (name "unconnected-(SV1-Pad26)") (class "Default")
      (node (ref "SV1") (pin "26") (pinfunction "26_26") (pintype "passive"))
    )
    (net (code "147") (name "unconnected-(SV1-Pad27)") (class "Default")
      (node (ref "SV1") (pin "27") (pinfunction "27_27") (pintype "passive"))
    )
    (net (code "148") (name "unconnected-(SV1-Pad28)") (class "Default")
      (node (ref "SV1") (pin "28") (pinfunction "28_28") (pintype "passive"))
    )
    (net (code "149") (name "unconnected-(SV1-Pad30)") (class "Default")
      (node (ref "SV1") (pin "30") (pinfunction "30_30") (pintype "passive"))
    )
    (net (code "150") (name "unconnected-(SV1-Pad31)") (class "Default")
      (node (ref "SV1") (pin "31") (pinfunction "31_31") (pintype "passive"))
    )
    (net (code "151") (name "unconnected-(SV1-Pad32)") (class "Default")
      (node (ref "SV1") (pin "32") (pinfunction "32_32") (pintype "passive"))
    )
    (net (code "152") (name "unconnected-(SV1-Pad33)") (class "Default")
      (node (ref "SV1") (pin "33") (pinfunction "33_33") (pintype "passive"))
    )
    (net (code "153") (name "unconnected-(SV1-Pad34)") (class "Default")
      (node (ref "SV1") (pin "34") (pinfunction "34_34") (pintype "passive"))
    )
    (net (code "154") (name "unconnected-(SV2-Pad1)") (class "Default")
      (node (ref "SV2") (pin "1") (pinfunction "1_1") (pintype "passive"))
    )
    (net (code "155") (name "unconnected-(SV2-Pad2)") (class "Default")
      (node (ref "SV2") (pin "2") (pinfunction "2_2") (pintype "passive"))
    )
    (net (code "156") (name "unconnected-(SV2-Pad3)") (class "Default")
      (node (ref "SV2") (pin "3") (pinfunction "3_3") (pintype "passive"))
    )
    (net (code "157") (name "unconnected-(SV2-Pad4)") (class "Default")
      (node (ref "SV2") (pin "4") (pinfunction "4_4") (pintype "passive"))
    )
    (net (code "158") (name "unconnected-(SV2-Pad5)") (class "Default")
      (node (ref "SV2") (pin "5") (pinfunction "5_5") (pintype "passive"))
    )
    (net (code "159") (name "unconnected-(SV2-Pad6)") (class "Default")
      (node (ref "SV2") (pin "6") (pinfunction "6_6") (pintype "passive"))
    )
    (net (code "160") (name "unconnected-(SV2-Pad7)") (class "Default")
      (node (ref "SV2") (pin "7") (pinfunction "7_7") (pintype "passive"))
    )
    (net (code "161") (name "unconnected-(SV2-Pad8)") (class "Default")
      (node (ref "SV2") (pin "8") (pinfunction "8_8") (pintype "passive"))
    )
    (net (code "162") (name "unconnected-(SV2-Pad10)") (class "Default")
      (node (ref "SV2") (pin "10") (pinfunction "10_10") (pintype "passive"))
    )
    (net (code "163") (name "unconnected-(SV2-Pad12)") (class "Default")
      (node (ref "SV2") (pin "12") (pinfunction "12_12") (pintype "passive"))
    )
    (net (code "164") (name "unconnected-(SV2-Pad13)") (class "Default")
      (node (ref "SV2") (pin "13") (pinfunction "13_13") (pintype "passive"))
    )
    (net (code "165") (name "unconnected-(SV2-Pad14)") (class "Default")
      (node (ref "SV2") (pin "14") (pinfunction "14_14") (pintype "passive"))
    )
    (net (code "166") (name "unconnected-(SV2-Pad15)") (class "Default")
      (node (ref "SV2") (pin "15") (pinfunction "15_15") (pintype "passive"))
    )
    (net (code "167") (name "unconnected-(SV2-Pad16)") (class "Default")
      (node (ref "SV2") (pin "16") (pinfunction "16_16") (pintype "passive"))
    )
    (net (code "168") (name "unconnected-(SV2-Pad17)") (class "Default")
      (node (ref "SV2") (pin "17") (pinfunction "17_17") (pintype "passive"))
    )
    (net (code "169") (name "unconnected-(SV2-Pad18)") (class "Default")
      (node (ref "SV2") (pin "18") (pinfunction "18_18") (pintype "passive"))
    )
    (net (code "170") (name "unconnected-(SV2-Pad19)") (class "Default")
      (node (ref "SV2") (pin "19") (pinfunction "19_19") (pintype "passive"))
    )
    (net (code "171") (name "unconnected-(SV2-Pad20)") (class "Default")
      (node (ref "SV2") (pin "20") (pinfunction "20_20") (pintype "passive"))
    )
    (net (code "172") (name "unconnected-(SV2-Pad21)") (class "Default")
      (node (ref "SV2") (pin "21") (pinfunction "21_21") (pintype "passive"))
    )
    (net (code "173") (name "unconnected-(SV2-Pad22)") (class "Default")
      (node (ref "SV2") (pin "22") (pinfunction "22_22") (pintype "passive"))
    )
    (net (code "174") (name "unconnected-(SV2-Pad23)") (class "Default")
      (node (ref "SV2") (pin "23") (pinfunction "23_23") (pintype "passive"))
    )
    (net (code "175") (name "unconnected-(SV2-Pad24)") (class "Default")
      (node (ref "SV2") (pin "24") (pinfunction "24_24") (pintype "passive"))
    )
    (net (code "176") (name "unconnected-(U4-SC4-Pad14)") (class "Default")
      (node (ref "U4") (pin "14") (pinfunction "SC4_14") (pintype "bidirectional"))
    )
    (net (code "177") (name "unconnected-(U4-SC5-Pad16)") (class "Default")
      (node (ref "U4") (pin "16") (pinfunction "SC5_16") (pintype "bidirectional"))
    )
    (net (code "178") (name "unconnected-(U4-SC6-Pad18)") (class "Default")
      (node (ref "U4") (pin "18") (pinfunction "SC6_18") (pintype "bidirectional"))
    )
    (net (code "179") (name "unconnected-(U4-SC7-Pad20)") (class "Default")
      (node (ref "U4") (pin "20") (pinfunction "SC7_20") (pintype "bidirectional"))
    )
    (net (code "180") (name "unconnected-(U4-SD4-Pad13)") (class "Default")
      (node (ref "U4") (pin "13") (pinfunction "SD4_13") (pintype "bidirectional"))
    )
    (net (code "181") (name "unconnected-(U4-SD5-Pad15)") (class "Default")
      (node (ref "U4") (pin "15") (pinfunction "SD5_15") (pintype "bidirectional"))
    )
    (net (code "182") (name "unconnected-(U4-SD6-Pad17)") (class "Default")
      (node (ref "U4") (pin "17") (pinfunction "SD6_17") (pintype "bidirectional"))
    )
    (net (code "183") (name "unconnected-(U4-SD7-Pad19)") (class "Default")
      (node (ref "U4") (pin "19") (pinfunction "SD7_19") (pintype "bidirectional"))
    )
  )
)
